# Backplane.net
KiCad netlist of a schematic drawn in EAGLE
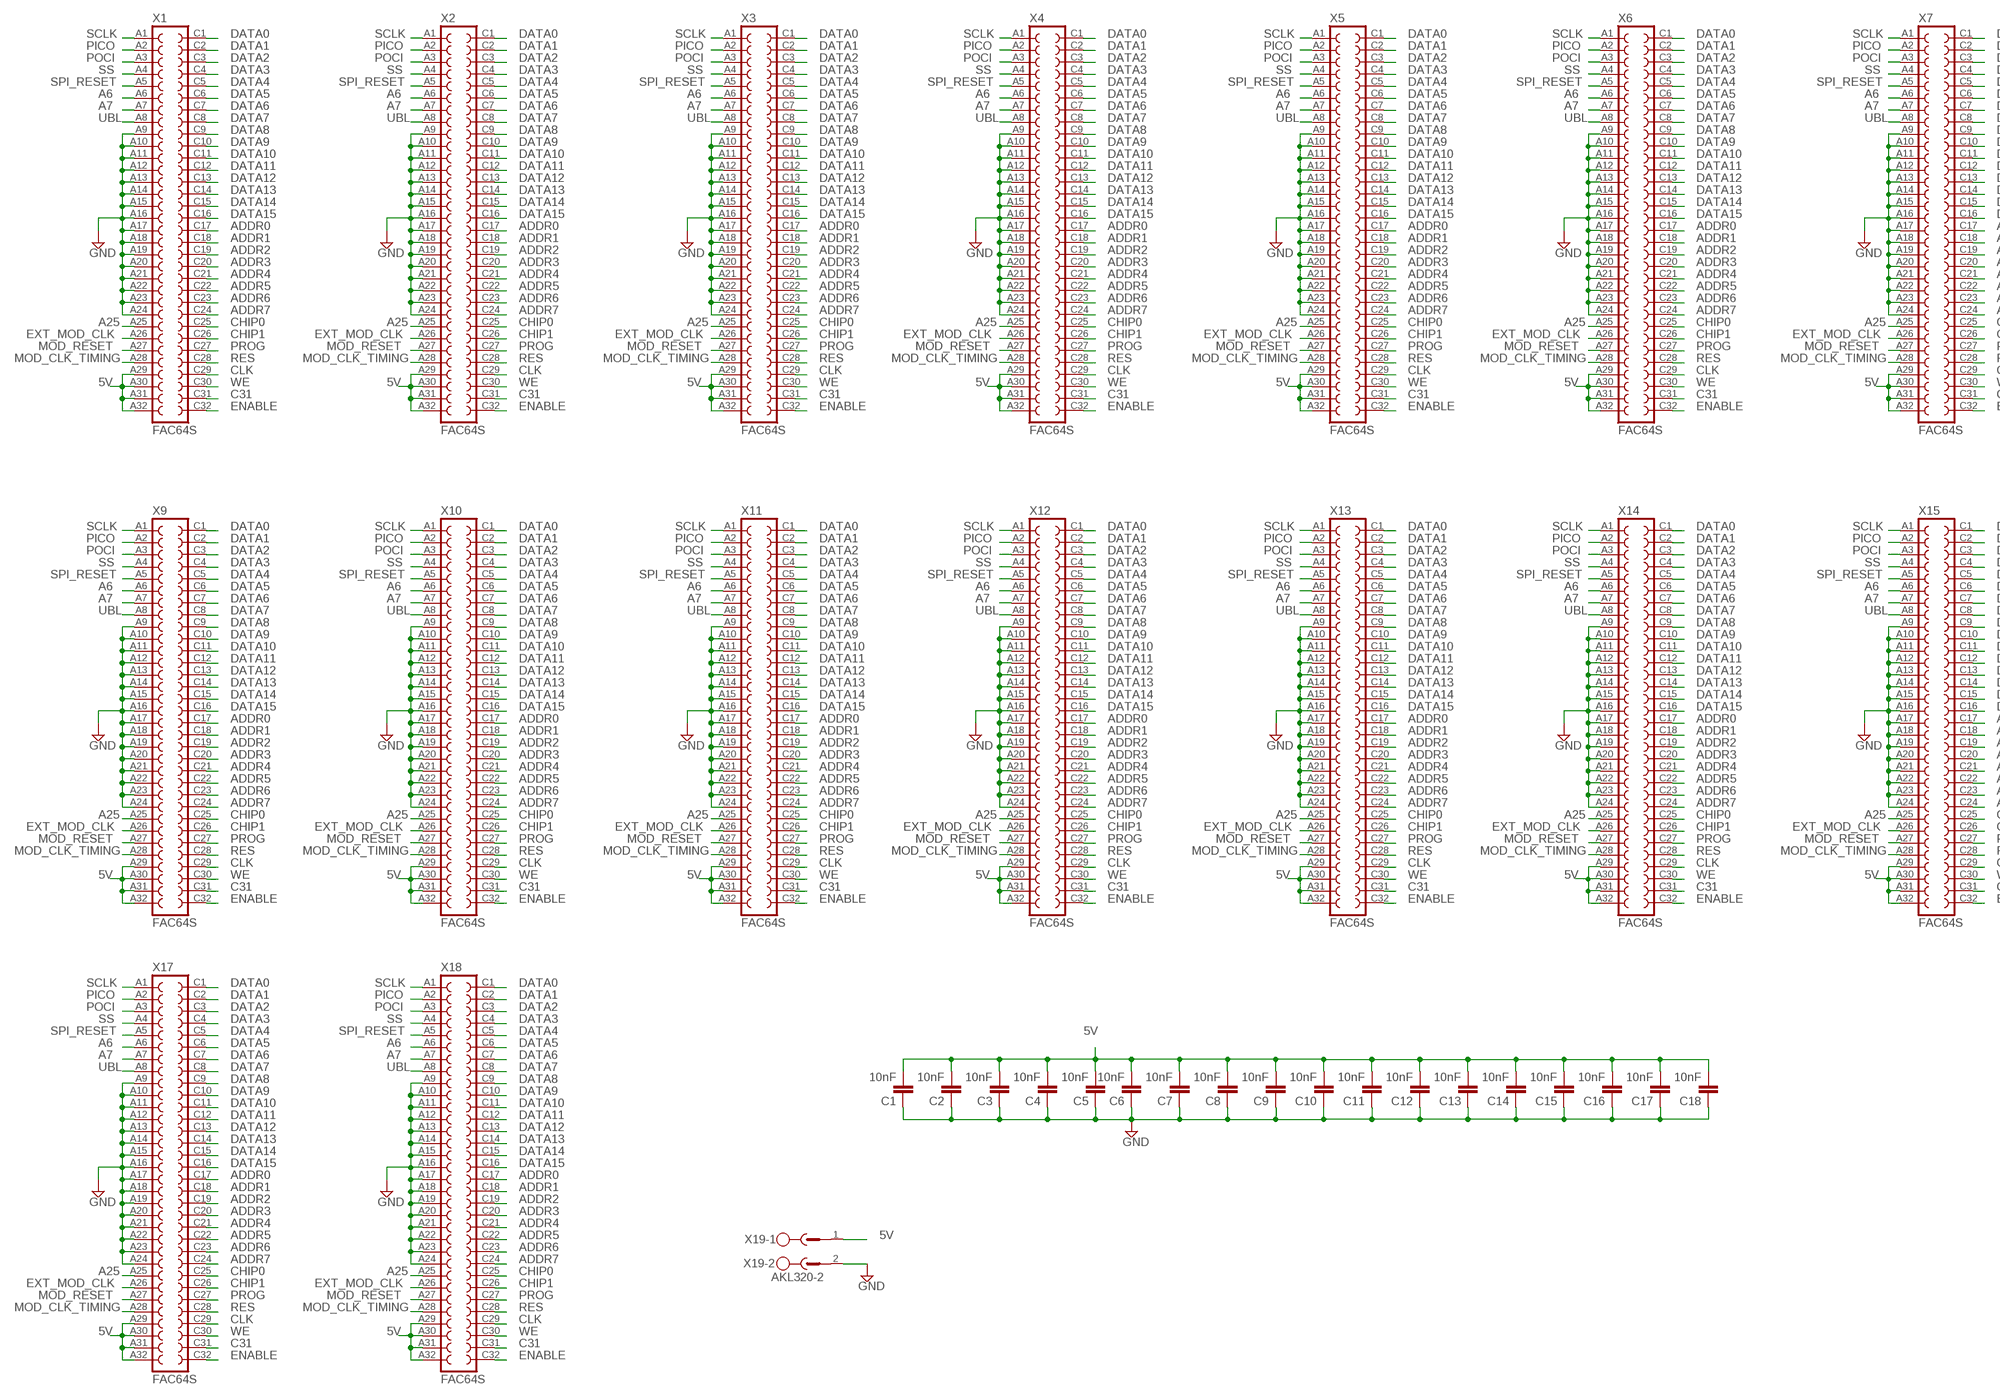
[diagram p0: schematic, sheet 1, part 1 of 2]
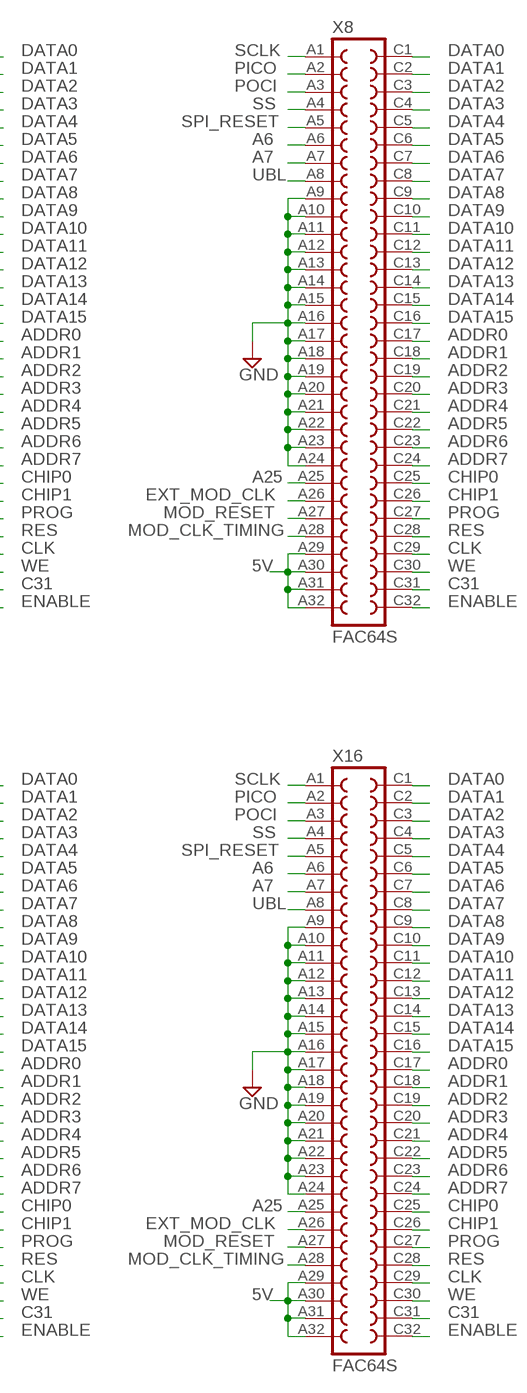
[diagram p1: schematic, sheet 1, part 2 of 2]

(export (version "E")
  (design (tool "Eeschema 10.0.6"))
  (components
    (comp (ref "C1")
      (value "10nF")
      (footprint "eagle-import:C0603")
      (libsource (lib "eagle-import") (part "C-EUC0603"))
    )
    (comp (ref "C2")
      (value "10nF")
      (footprint "eagle-import:C0603")
      (libsource (lib "eagle-import") (part "C-EUC0603"))
    )
    (comp (ref "C3")
      (value "10nF")
      (footprint "eagle-import:C0603")
      (libsource (lib "eagle-import") (part "C-EUC0603"))
    )
    (comp (ref "C4")
      (value "10nF")
      (footprint "eagle-import:C0603")
      (libsource (lib "eagle-import") (part "C-EUC0603"))
    )
    (comp (ref "C5")
      (value "10nF")
      (footprint "eagle-import:C0603")
      (libsource (lib "eagle-import") (part "C-EUC0603"))
    )
    (comp (ref "C6")
      (value "10nF")
      (footprint "eagle-import:C0603")
      (libsource (lib "eagle-import") (part "C-EUC0603"))
    )
    (comp (ref "C7")
      (value "10nF")
      (footprint "eagle-import:C0603")
      (libsource (lib "eagle-import") (part "C-EUC0603"))
    )
    (comp (ref "C8")
      (value "10nF")
      (footprint "eagle-import:C0603")
      (libsource (lib "eagle-import") (part "C-EUC0603"))
    )
    (comp (ref "C9")
      (value "10nF")
      (footprint "eagle-import:C0603")
      (libsource (lib "eagle-import") (part "C-EUC0603"))
    )
    (comp (ref "C10")
      (value "10nF")
      (footprint "eagle-import:C0603")
      (libsource (lib "eagle-import") (part "C-EUC0603"))
    )
    (comp (ref "C11")
      (value "10nF")
      (footprint "eagle-import:C0603")
      (libsource (lib "eagle-import") (part "C-EUC0603"))
    )
    (comp (ref "C12")
      (value "10nF")
      (footprint "eagle-import:C0603")
      (libsource (lib "eagle-import") (part "C-EUC0603"))
    )
    (comp (ref "C13")
      (value "10nF")
      (footprint "eagle-import:C0603")
      (libsource (lib "eagle-import") (part "C-EUC0603"))
    )
    (comp (ref "C14")
      (value "10nF")
      (footprint "eagle-import:C0603")
      (libsource (lib "eagle-import") (part "C-EUC0603"))
    )
    (comp (ref "C15")
      (value "10nF")
      (footprint "eagle-import:C0603")
      (libsource (lib "eagle-import") (part "C-EUC0603"))
    )
    (comp (ref "C16")
      (value "10nF")
      (footprint "eagle-import:C0603")
      (libsource (lib "eagle-import") (part "C-EUC0603"))
    )
    (comp (ref "C17")
      (value "10nF")
      (footprint "eagle-import:C0603")
      (libsource (lib "eagle-import") (part "C-EUC0603"))
    )
    (comp (ref "C18")
      (value "10nF")
      (footprint "eagle-import:C0603")
      (libsource (lib "eagle-import") (part "C-EUC0603"))
    )
    (comp (ref "X1")
      (value "FAC64S")
      (footprint "eagle-import:FAC64S")
      (libsource (lib "eagle-import") (part "FAC64S"))
    )
    (comp (ref "X2")
      (value "FAC64S")
      (footprint "eagle-import:FAC64S")
      (libsource (lib "eagle-import") (part "FAC64S"))
    )
    (comp (ref "X3")
      (value "FAC64S")
      (footprint "eagle-import:FAC64S")
      (libsource (lib "eagle-import") (part "FAC64S"))
    )
    (comp (ref "X4")
      (value "FAC64S")
      (footprint "eagle-import:FAC64S")
      (libsource (lib "eagle-import") (part "FAC64S"))
    )
    (comp (ref "X5")
      (value "FAC64S")
      (footprint "eagle-import:FAC64S")
      (libsource (lib "eagle-import") (part "FAC64S"))
    )
    (comp (ref "X6")
      (value "FAC64S")
      (footprint "eagle-import:FAC64S")
      (libsource (lib "eagle-import") (part "FAC64S"))
    )
    (comp (ref "X7")
      (value "FAC64S")
      (footprint "eagle-import:FAC64S")
      (libsource (lib "eagle-import") (part "FAC64S"))
    )
    (comp (ref "X8")
      (value "FAC64S")
      (footprint "eagle-import:FAC64S")
      (libsource (lib "eagle-import") (part "FAC64S"))
    )
    (comp (ref "X9")
      (value "FAC64S")
      (footprint "eagle-import:FAC64S")
      (libsource (lib "eagle-import") (part "FAC64S"))
    )
    (comp (ref "X10")
      (value "FAC64S")
      (footprint "eagle-import:FAC64S")
      (libsource (lib "eagle-import") (part "FAC64S"))
    )
    (comp (ref "X11")
      (value "FAC64S")
      (footprint "eagle-import:FAC64S")
      (libsource (lib "eagle-import") (part "FAC64S"))
    )
    (comp (ref "X12")
      (value "FAC64S")
      (footprint "eagle-import:FAC64S")
      (libsource (lib "eagle-import") (part "FAC64S"))
    )
    (comp (ref "X13")
      (value "FAC64S")
      (footprint "eagle-import:FAC64S")
      (libsource (lib "eagle-import") (part "FAC64S"))
    )
    (comp (ref "X14")
      (value "FAC64S")
      (footprint "eagle-import:FAC64S")
      (libsource (lib "eagle-import") (part "FAC64S"))
    )
    (comp (ref "X15")
      (value "FAC64S")
      (footprint "eagle-import:FAC64S")
      (libsource (lib "eagle-import") (part "FAC64S"))
    )
    (comp (ref "X16")
      (value "FAC64S")
      (footprint "eagle-import:FAC64S")
      (libsource (lib "eagle-import") (part "FAC64S"))
    )
    (comp (ref "X17")
      (value "FAC64S")
      (footprint "eagle-import:FAC64S")
      (libsource (lib "eagle-import") (part "FAC64S"))
    )
    (comp (ref "X18")
      (value "FAC64S")
      (footprint "eagle-import:FAC64S")
      (libsource (lib "eagle-import") (part "FAC64S"))
    )
    (comp (ref "X19")
      (value "AKL320-2")
      (footprint "eagle-import:MSTBV2")
      (libsource (lib "eagle-import") (part "MSTBV2"))
    )
  )
  (nets
    (net (code "1") (name "/5V") (class "Default")
      (node (ref "C1") (pin "2") (pinfunction "2_2") (pintype "passive"))
      (node (ref "C10") (pin "2") (pinfunction "2_2") (pintype "passive"))
      (node (ref "C11") (pin "2") (pinfunction "2_2") (pintype "passive"))
      (node (ref "C12") (pin "2") (pinfunction "2_2") (pintype "passive"))
      (node (ref "C13") (pin "2") (pinfunction "2_2") (pintype "passive"))
      (node (ref "C14") (pin "2") (pinfunction "2_2") (pintype "passive"))
      (node (ref "C15") (pin "2") (pinfunction "2_2") (pintype "passive"))
      (node (ref "C16") (pin "2") (pinfunction "2_2") (pintype "passive"))
      (node (ref "C17") (pin "2") (pinfunction "2_2") (pintype "passive"))
      (node (ref "C18") (pin "2") (pinfunction "2_2") (pintype "passive"))
      (node (ref "C2") (pin "2") (pinfunction "2_2") (pintype "passive"))
      (node (ref "C3") (pin "2") (pinfunction "2_2") (pintype "passive"))
      (node (ref "C4") (pin "2") (pinfunction "2_2") (pintype "passive"))
      (node (ref "C5") (pin "2") (pinfunction "2_2") (pintype "passive"))
      (node (ref "C6") (pin "2") (pinfunction "2_2") (pintype "passive"))
      (node (ref "C7") (pin "2") (pinfunction "2_2") (pintype "passive"))
      (node (ref "C8") (pin "2") (pinfunction "2_2") (pintype "passive"))
      (node (ref "C9") (pin "2") (pinfunction "2_2") (pintype "passive"))
      (node (ref "X1") (pin "A29") (pinfunction "A29_A29") (pintype "passive"))
      (node (ref "X1") (pin "A30") (pinfunction "A30_A30") (pintype "passive"))
      (node (ref "X1") (pin "A31") (pinfunction "A31_A31") (pintype "passive"))
      (node (ref "X1") (pin "A32") (pinfunction "A32_A32") (pintype "passive"))
      (node (ref "X10") (pin "A29") (pinfunction "A29_A29") (pintype "passive"))
      (node (ref "X10") (pin "A30") (pinfunction "A30_A30") (pintype "passive"))
      (node (ref "X10") (pin "A31") (pinfunction "A31_A31") (pintype "passive"))
      (node (ref "X10") (pin "A32") (pinfunction "A32_A32") (pintype "passive"))
      (node (ref "X11") (pin "A29") (pinfunction "A29_A29") (pintype "passive"))
      (node (ref "X11") (pin "A30") (pinfunction "A30_A30") (pintype "passive"))
      (node (ref "X11") (pin "A31") (pinfunction "A31_A31") (pintype "passive"))
      (node (ref "X11") (pin "A32") (pinfunction "A32_A32") (pintype "passive"))
      (node (ref "X12") (pin "A29") (pinfunction "A29_A29") (pintype "passive"))
      (node (ref "X12") (pin "A30") (pinfunction "A30_A30") (pintype "passive"))
      (node (ref "X12") (pin "A31") (pinfunction "A31_A31") (pintype "passive"))
      (node (ref "X12") (pin "A32") (pinfunction "A32_A32") (pintype "passive"))
      (node (ref "X13") (pin "A29") (pinfunction "A29_A29") (pintype "passive"))
      (node (ref "X13") (pin "A30") (pinfunction "A30_A30") (pintype "passive"))
      (node (ref "X13") (pin "A31") (pinfunction "A31_A31") (pintype "passive"))
      (node (ref "X13") (pin "A32") (pinfunction "A32_A32") (pintype "passive"))
      (node (ref "X14") (pin "A29") (pinfunction "A29_A29") (pintype "passive"))
      (node (ref "X14") (pin "A30") (pinfunction "A30_A30") (pintype "passive"))
      (node (ref "X14") (pin "A31") (pinfunction "A31_A31") (pintype "passive"))
      (node (ref "X14") (pin "A32") (pinfunction "A32_A32") (pintype "passive"))
      (node (ref "X15") (pin "A29") (pinfunction "A29_A29") (pintype "passive"))
      (node (ref "X15") (pin "A30") (pinfunction "A30_A30") (pintype "passive"))
      (node (ref "X15") (pin "A31") (pinfunction "A31_A31") (pintype "passive"))
      (node (ref "X15") (pin "A32") (pinfunction "A32_A32") (pintype "passive"))
      (node (ref "X16") (pin "A29") (pinfunction "A29_A29") (pintype "passive"))
      (node (ref "X16") (pin "A30") (pinfunction "A30_A30") (pintype "passive"))
      (node (ref "X16") (pin "A31") (pinfunction "A31_A31") (pintype "passive"))
      (node (ref "X16") (pin "A32") (pinfunction "A32_A32") (pintype "passive"))
      (node (ref "X17") (pin "A29") (pinfunction "A29_A29") (pintype "passive"))
      (node (ref "X17") (pin "A30") (pinfunction "A30_A30") (pintype "passive"))
      (node (ref "X17") (pin "A31") (pinfunction "A31_A31") (pintype "passive"))
      (node (ref "X17") (pin "A32") (pinfunction "A32_A32") (pintype "passive"))
      (node (ref "X18") (pin "A29") (pinfunction "A29_A29") (pintype "passive"))
      (node (ref "X18") (pin "A30") (pinfunction "A30_A30") (pintype "passive"))
      (node (ref "X18") (pin "A31") (pinfunction "A31_A31") (pintype "passive"))
      (node (ref "X18") (pin "A32") (pinfunction "A32_A32") (pintype "passive"))
      (node (ref "X19") (pin "1") (pinfunction "SK_1") (pintype "passive"))
      (node (ref "X2") (pin "A29") (pinfunction "A29_A29") (pintype "passive"))
      (node (ref "X2") (pin "A30") (pinfunction "A30_A30") (pintype "passive"))
      (node (ref "X2") (pin "A31") (pinfunction "A31_A31") (pintype "passive"))
      (node (ref "X2") (pin "A32") (pinfunction "A32_A32") (pintype "passive"))
      (node (ref "X3") (pin "A29") (pinfunction "A29_A29") (pintype "passive"))
      (node (ref "X3") (pin "A30") (pinfunction "A30_A30") (pintype "passive"))
      (node (ref "X3") (pin "A31") (pinfunction "A31_A31") (pintype "passive"))
      (node (ref "X3") (pin "A32") (pinfunction "A32_A32") (pintype "passive"))
      (node (ref "X4") (pin "A29") (pinfunction "A29_A29") (pintype "passive"))
      (node (ref "X4") (pin "A30") (pinfunction "A30_A30") (pintype "passive"))
      (node (ref "X4") (pin "A31") (pinfunction "A31_A31") (pintype "passive"))
      (node (ref "X4") (pin "A32") (pinfunction "A32_A32") (pintype "passive"))
      (node (ref "X5") (pin "A29") (pinfunction "A29_A29") (pintype "passive"))
      (node (ref "X5") (pin "A30") (pinfunction "A30_A30") (pintype "passive"))
      (node (ref "X5") (pin "A31") (pinfunction "A31_A31") (pintype "passive"))
      (node (ref "X5") (pin "A32") (pinfunction "A32_A32") (pintype "passive"))
      (node (ref "X6") (pin "A29") (pinfunction "A29_A29") (pintype "passive"))
      (node (ref "X6") (pin "A30") (pinfunction "A30_A30") (pintype "passive"))
      (node (ref "X6") (pin "A31") (pinfunction "A31_A31") (pintype "passive"))
      (node (ref "X6") (pin "A32") (pinfunction "A32_A32") (pintype "passive"))
      (node (ref "X7") (pin "A29") (pinfunction "A29_A29") (pintype "passive"))
      (node (ref "X7") (pin "A30") (pinfunction "A30_A30") (pintype "passive"))
      (node (ref "X7") (pin "A31") (pinfunction "A31_A31") (pintype "passive"))
      (node (ref "X7") (pin "A32") (pinfunction "A32_A32") (pintype "passive"))
      (node (ref "X8") (pin "A29") (pinfunction "A29_A29") (pintype "passive"))
      (node (ref "X8") (pin "A30") (pinfunction "A30_A30") (pintype "passive"))
      (node (ref "X8") (pin "A31") (pinfunction "A31_A31") (pintype "passive"))
      (node (ref "X8") (pin "A32") (pinfunction "A32_A32") (pintype "passive"))
      (node (ref "X9") (pin "A29") (pinfunction "A29_A29") (pintype "passive"))
      (node (ref "X9") (pin "A30") (pinfunction "A30_A30") (pintype "passive"))
      (node (ref "X9") (pin "A31") (pinfunction "A31_A31") (pintype "passive"))
      (node (ref "X9") (pin "A32") (pinfunction "A32_A32") (pintype "passive"))
    )
    (net (code "2") (name "/A6") (class "Default")
      (node (ref "X1") (pin "A6") (pinfunction "A6_A6") (pintype "passive"))
      (node (ref "X10") (pin "A6") (pinfunction "A6_A6") (pintype "passive"))
      (node (ref "X11") (pin "A6") (pinfunction "A6_A6") (pintype "passive"))
      (node (ref "X12") (pin "A6") (pinfunction "A6_A6") (pintype "passive"))
      (node (ref "X13") (pin "A6") (pinfunction "A6_A6") (pintype "passive"))
      (node (ref "X14") (pin "A6") (pinfunction "A6_A6") (pintype "passive"))
      (node (ref "X15") (pin "A6") (pinfunction "A6_A6") (pintype "passive"))
      (node (ref "X16") (pin "A6") (pinfunction "A6_A6") (pintype "passive"))
      (node (ref "X17") (pin "A6") (pinfunction "A6_A6") (pintype "passive"))
      (node (ref "X18") (pin "A6") (pinfunction "A6_A6") (pintype "passive"))
      (node (ref "X2") (pin "A6") (pinfunction "A6_A6") (pintype "passive"))
      (node (ref "X3") (pin "A6") (pinfunction "A6_A6") (pintype "passive"))
      (node (ref "X4") (pin "A6") (pinfunction "A6_A6") (pintype "passive"))
      (node (ref "X5") (pin "A6") (pinfunction "A6_A6") (pintype "passive"))
      (node (ref "X6") (pin "A6") (pinfunction "A6_A6") (pintype "passive"))
      (node (ref "X7") (pin "A6") (pinfunction "A6_A6") (pintype "passive"))
      (node (ref "X8") (pin "A6") (pinfunction "A6_A6") (pintype "passive"))
      (node (ref "X9") (pin "A6") (pinfunction "A6_A6") (pintype "passive"))
    )
    (net (code "3") (name "/A7") (class "Default")
      (node (ref "X1") (pin "A7") (pinfunction "A7_A7") (pintype "passive"))
      (node (ref "X10") (pin "A7") (pinfunction "A7_A7") (pintype "passive"))
      (node (ref "X11") (pin "A7") (pinfunction "A7_A7") (pintype "passive"))
      (node (ref "X12") (pin "A7") (pinfunction "A7_A7") (pintype "passive"))
      (node (ref "X13") (pin "A7") (pinfunction "A7_A7") (pintype "passive"))
      (node (ref "X14") (pin "A7") (pinfunction "A7_A7") (pintype "passive"))
      (node (ref "X15") (pin "A7") (pinfunction "A7_A7") (pintype "passive"))
      (node (ref "X16") (pin "A7") (pinfunction "A7_A7") (pintype "passive"))
      (node (ref "X17") (pin "A7") (pinfunction "A7_A7") (pintype "passive"))
      (node (ref "X18") (pin "A7") (pinfunction "A7_A7") (pintype "passive"))
      (node (ref "X2") (pin "A7") (pinfunction "A7_A7") (pintype "passive"))
      (node (ref "X3") (pin "A7") (pinfunction "A7_A7") (pintype "passive"))
      (node (ref "X4") (pin "A7") (pinfunction "A7_A7") (pintype "passive"))
      (node (ref "X5") (pin "A7") (pinfunction "A7_A7") (pintype "passive"))
      (node (ref "X6") (pin "A7") (pinfunction "A7_A7") (pintype "passive"))
      (node (ref "X7") (pin "A7") (pinfunction "A7_A7") (pintype "passive"))
      (node (ref "X8") (pin "A7") (pinfunction "A7_A7") (pintype "passive"))
      (node (ref "X9") (pin "A7") (pinfunction "A7_A7") (pintype "passive"))
    )
    (net (code "4") (name "/A25") (class "Default")
      (node (ref "X1") (pin "A25") (pinfunction "A25_A25") (pintype "passive"))
      (node (ref "X10") (pin "A25") (pinfunction "A25_A25") (pintype "passive"))
      (node (ref "X11") (pin "A25") (pinfunction "A25_A25") (pintype "passive"))
      (node (ref "X12") (pin "A25") (pinfunction "A25_A25") (pintype "passive"))
      (node (ref "X13") (pin "A25") (pinfunction "A25_A25") (pintype "passive"))
      (node (ref "X14") (pin "A25") (pinfunction "A25_A25") (pintype "passive"))
      (node (ref "X15") (pin "A25") (pinfunction "A25_A25") (pintype "passive"))
      (node (ref "X16") (pin "A25") (pinfunction "A25_A25") (pintype "passive"))
      (node (ref "X17") (pin "A25") (pinfunction "A25_A25") (pintype "passive"))
      (node (ref "X18") (pin "A25") (pinfunction "A25_A25") (pintype "passive"))
      (node (ref "X2") (pin "A25") (pinfunction "A25_A25") (pintype "passive"))
      (node (ref "X3") (pin "A25") (pinfunction "A25_A25") (pintype "passive"))
      (node (ref "X4") (pin "A25") (pinfunction "A25_A25") (pintype "passive"))
      (node (ref "X5") (pin "A25") (pinfunction "A25_A25") (pintype "passive"))
      (node (ref "X6") (pin "A25") (pinfunction "A25_A25") (pintype "passive"))
      (node (ref "X7") (pin "A25") (pinfunction "A25_A25") (pintype "passive"))
      (node (ref "X8") (pin "A25") (pinfunction "A25_A25") (pintype "passive"))
      (node (ref "X9") (pin "A25") (pinfunction "A25_A25") (pintype "passive"))
    )
    (net (code "5") (name "/ADDR0") (class "Default")
      (node (ref "X1") (pin "C17") (pinfunction "C17_C17") (pintype "passive"))
      (node (ref "X10") (pin "C17") (pinfunction "C17_C17") (pintype "passive"))
      (node (ref "X11") (pin "C17") (pinfunction "C17_C17") (pintype "passive"))
      (node (ref "X12") (pin "C17") (pinfunction "C17_C17") (pintype "passive"))
      (node (ref "X13") (pin "C17") (pinfunction "C17_C17") (pintype "passive"))
      (node (ref "X14") (pin "C17") (pinfunction "C17_C17") (pintype "passive"))
      (node (ref "X15") (pin "C17") (pinfunction "C17_C17") (pintype "passive"))
      (node (ref "X16") (pin "C17") (pinfunction "C17_C17") (pintype "passive"))
      (node (ref "X17") (pin "C17") (pinfunction "C17_C17") (pintype "passive"))
      (node (ref "X18") (pin "C17") (pinfunction "C17_C17") (pintype "passive"))
      (node (ref "X2") (pin "C17") (pinfunction "C17_C17") (pintype "passive"))
      (node (ref "X3") (pin "C17") (pinfunction "C17_C17") (pintype "passive"))
      (node (ref "X4") (pin "C17") (pinfunction "C17_C17") (pintype "passive"))
      (node (ref "X5") (pin "C17") (pinfunction "C17_C17") (pintype "passive"))
      (node (ref "X6") (pin "C17") (pinfunction "C17_C17") (pintype "passive"))
      (node (ref "X7") (pin "C17") (pinfunction "C17_C17") (pintype "passive"))
      (node (ref "X8") (pin "C17") (pinfunction "C17_C17") (pintype "passive"))
      (node (ref "X9") (pin "C17") (pinfunction "C17_C17") (pintype "passive"))
    )
    (net (code "6") (name "/ADDR1") (class "Default")
      (node (ref "X1") (pin "C18") (pinfunction "C18_C18") (pintype "passive"))
      (node (ref "X10") (pin "C18") (pinfunction "C18_C18") (pintype "passive"))
      (node (ref "X11") (pin "C18") (pinfunction "C18_C18") (pintype "passive"))
      (node (ref "X12") (pin "C18") (pinfunction "C18_C18") (pintype "passive"))
      (node (ref "X13") (pin "C18") (pinfunction "C18_C18") (pintype "passive"))
      (node (ref "X14") (pin "C18") (pinfunction "C18_C18") (pintype "passive"))
      (node (ref "X15") (pin "C18") (pinfunction "C18_C18") (pintype "passive"))
      (node (ref "X16") (pin "C18") (pinfunction "C18_C18") (pintype "passive"))
      (node (ref "X17") (pin "C18") (pinfunction "C18_C18") (pintype "passive"))
      (node (ref "X18") (pin "C18") (pinfunction "C18_C18") (pintype "passive"))
      (node (ref "X2") (pin "C18") (pinfunction "C18_C18") (pintype "passive"))
      (node (ref "X3") (pin "C18") (pinfunction "C18_C18") (pintype "passive"))
      (node (ref "X4") (pin "C18") (pinfunction "C18_C18") (pintype "passive"))
      (node (ref "X5") (pin "C18") (pinfunction "C18_C18") (pintype "passive"))
      (node (ref "X6") (pin "C18") (pinfunction "C18_C18") (pintype "passive"))
      (node (ref "X7") (pin "C18") (pinfunction "C18_C18") (pintype "passive"))
      (node (ref "X8") (pin "C18") (pinfunction "C18_C18") (pintype "passive"))
      (node (ref "X9") (pin "C18") (pinfunction "C18_C18") (pintype "passive"))
    )
    (net (code "7") (name "/ADDR2") (class "Default")
      (node (ref "X1") (pin "C19") (pinfunction "C19_C19") (pintype "passive"))
      (node (ref "X10") (pin "C19") (pinfunction "C19_C19") (pintype "passive"))
      (node (ref "X11") (pin "C19") (pinfunction "C19_C19") (pintype "passive"))
      (node (ref "X12") (pin "C19") (pinfunction "C19_C19") (pintype "passive"))
      (node (ref "X13") (pin "C19") (pinfunction "C19_C19") (pintype "passive"))
      (node (ref "X14") (pin "C19") (pinfunction "C19_C19") (pintype "passive"))
      (node (ref "X15") (pin "C19") (pinfunction "C19_C19") (pintype "passive"))
      (node (ref "X16") (pin "C19") (pinfunction "C19_C19") (pintype "passive"))
      (node (ref "X17") (pin "C19") (pinfunction "C19_C19") (pintype "passive"))
      (node (ref "X18") (pin "C19") (pinfunction "C19_C19") (pintype "passive"))
      (node (ref "X2") (pin "C19") (pinfunction "C19_C19") (pintype "passive"))
      (node (ref "X3") (pin "C19") (pinfunction "C19_C19") (pintype "passive"))
      (node (ref "X4") (pin "C19") (pinfunction "C19_C19") (pintype "passive"))
      (node (ref "X5") (pin "C19") (pinfunction "C19_C19") (pintype "passive"))
      (node (ref "X6") (pin "C19") (pinfunction "C19_C19") (pintype "passive"))
      (node (ref "X7") (pin "C19") (pinfunction "C19_C19") (pintype "passive"))
      (node (ref "X8") (pin "C19") (pinfunction "C19_C19") (pintype "passive"))
      (node (ref "X9") (pin "C19") (pinfunction "C19_C19") (pintype "passive"))
    )
    (net (code "8") (name "/ADDR3") (class "Default")
      (node (ref "X1") (pin "C20") (pinfunction "C20_C20") (pintype "passive"))
      (node (ref "X10") (pin "C20") (pinfunction "C20_C20") (pintype "passive"))
      (node (ref "X11") (pin "C20") (pinfunction "C20_C20") (pintype "passive"))
      (node (ref "X12") (pin "C20") (pinfunction "C20_C20") (pintype "passive"))
      (node (ref "X13") (pin "C20") (pinfunction "C20_C20") (pintype "passive"))
      (node (ref "X14") (pin "C20") (pinfunction "C20_C20") (pintype "passive"))
      (node (ref "X15") (pin "C20") (pinfunction "C20_C20") (pintype "passive"))
      (node (ref "X16") (pin "C20") (pinfunction "C20_C20") (pintype "passive"))
      (node (ref "X17") (pin "C20") (pinfunction "C20_C20") (pintype "passive"))
      (node (ref "X18") (pin "C20") (pinfunction "C20_C20") (pintype "passive"))
      (node (ref "X2") (pin "C20") (pinfunction "C20_C20") (pintype "passive"))
      (node (ref "X3") (pin "C20") (pinfunction "C20_C20") (pintype "passive"))
      (node (ref "X4") (pin "C20") (pinfunction "C20_C20") (pintype "passive"))
      (node (ref "X5") (pin "C20") (pinfunction "C20_C20") (pintype "passive"))
      (node (ref "X6") (pin "C20") (pinfunction "C20_C20") (pintype "passive"))
      (node (ref "X7") (pin "C20") (pinfunction "C20_C20") (pintype "passive"))
      (node (ref "X8") (pin "C20") (pinfunction "C20_C20") (pintype "passive"))
      (node (ref "X9") (pin "C20") (pinfunction "C20_C20") (pintype "passive"))
    )
    (net (code "9") (name "/ADDR4") (class "Default")
      (node (ref "X1") (pin "C21") (pinfunction "C21_C21") (pintype "passive"))
      (node (ref "X10") (pin "C21") (pinfunction "C21_C21") (pintype "passive"))
      (node (ref "X11") (pin "C21") (pinfunction "C21_C21") (pintype "passive"))
      (node (ref "X12") (pin "C21") (pinfunction "C21_C21") (pintype "passive"))
      (node (ref "X13") (pin "C21") (pinfunction "C21_C21") (pintype "passive"))
      (node (ref "X14") (pin "C21") (pinfunction "C21_C21") (pintype "passive"))
      (node (ref "X15") (pin "C21") (pinfunction "C21_C21") (pintype "passive"))
      (node (ref "X16") (pin "C21") (pinfunction "C21_C21") (pintype "passive"))
      (node (ref "X17") (pin "C21") (pinfunction "C21_C21") (pintype "passive"))
      (node (ref "X18") (pin "C21") (pinfunction "C21_C21") (pintype "passive"))
      (node (ref "X2") (pin "C21") (pinfunction "C21_C21") (pintype "passive"))
      (node (ref "X3") (pin "C21") (pinfunction "C21_C21") (pintype "passive"))
      (node (ref "X4") (pin "C21") (pinfunction "C21_C21") (pintype "passive"))
      (node (ref "X5") (pin "C21") (pinfunction "C21_C21") (pintype "passive"))
      (node (ref "X6") (pin "C21") (pinfunction "C21_C21") (pintype "passive"))
      (node (ref "X7") (pin "C21") (pinfunction "C21_C21") (pintype "passive"))
      (node (ref "X8") (pin "C21") (pinfunction "C21_C21") (pintype "passive"))
      (node (ref "X9") (pin "C21") (pinfunction "C21_C21") (pintype "passive"))
    )
    (net (code "10") (name "/ADDR5") (class "Default")
      (node (ref "X1") (pin "C22") (pinfunction "C22_C22") (pintype "passive"))
      (node (ref "X10") (pin "C22") (pinfunction "C22_C22") (pintype "passive"))
      (node (ref "X11") (pin "C22") (pinfunction "C22_C22") (pintype "passive"))
      (node (ref "X12") (pin "C22") (pinfunction "C22_C22") (pintype "passive"))
      (node (ref "X13") (pin "C22") (pinfunction "C22_C22") (pintype "passive"))
      (node (ref "X14") (pin "C22") (pinfunction "C22_C22") (pintype "passive"))
      (node (ref "X15") (pin "C22") (pinfunction "C22_C22") (pintype "passive"))
      (node (ref "X16") (pin "C22") (pinfunction "C22_C22") (pintype "passive"))
      (node (ref "X17") (pin "C22") (pinfunction "C22_C22") (pintype "passive"))
      (node (ref "X18") (pin "C22") (pinfunction "C22_C22") (pintype "passive"))
      (node (ref "X2") (pin "C22") (pinfunction "C22_C22") (pintype "passive"))
      (node (ref "X3") (pin "C22") (pinfunction "C22_C22") (pintype "passive"))
      (node (ref "X4") (pin "C22") (pinfunction "C22_C22") (pintype "passive"))
      (node (ref "X5") (pin "C22") (pinfunction "C22_C22") (pintype "passive"))
      (node (ref "X6") (pin "C22") (pinfunction "C22_C22") (pintype "passive"))
      (node (ref "X7") (pin "C22") (pinfunction "C22_C22") (pintype "passive"))
      (node (ref "X8") (pin "C22") (pinfunction "C22_C22") (pintype "passive"))
      (node (ref "X9") (pin "C22") (pinfunction "C22_C22") (pintype "passive"))
    )
    (net (code "11") (name "/ADDR6") (class "Default")
      (node (ref "X1") (pin "C23") (pinfunction "C23_C23") (pintype "passive"))
      (node (ref "X10") (pin "C23") (pinfunction "C23_C23") (pintype "passive"))
      (node (ref "X11") (pin "C23") (pinfunction "C23_C23") (pintype "passive"))
      (node (ref "X12") (pin "C23") (pinfunction "C23_C23") (pintype "passive"))
      (node (ref "X13") (pin "C23") (pinfunction "C23_C23") (pintype "passive"))
      (node (ref "X14") (pin "C23") (pinfunction "C23_C23") (pintype "passive"))
      (node (ref "X15") (pin "C23") (pinfunction "C23_C23") (pintype "passive"))
      (node (ref "X16") (pin "C23") (pinfunction "C23_C23") (pintype "passive"))
      (node (ref "X17") (pin "C23") (pinfunction "C23_C23") (pintype "passive"))
      (node (ref "X18") (pin "C23") (pinfunction "C23_C23") (pintype "passive"))
      (node (ref "X2") (pin "C23") (pinfunction "C23_C23") (pintype "passive"))
      (node (ref "X3") (pin "C23") (pinfunction "C23_C23") (pintype "passive"))
      (node (ref "X4") (pin "C23") (pinfunction "C23_C23") (pintype "passive"))
      (node (ref "X5") (pin "C23") (pinfunction "C23_C23") (pintype "passive"))
      (node (ref "X6") (pin "C23") (pinfunction "C23_C23") (pintype "passive"))
      (node (ref "X7") (pin "C23") (pinfunction "C23_C23") (pintype "passive"))
      (node (ref "X8") (pin "C23") (pinfunction "C23_C23") (pintype "passive"))
      (node (ref "X9") (pin "C23") (pinfunction "C23_C23") (pintype "passive"))
    )
    (net (code "12") (name "/ADDR7") (class "Default")
      (node (ref "X1") (pin "C24") (pinfunction "C24_C24") (pintype "passive"))
      (node (ref "X10") (pin "C24") (pinfunction "C24_C24") (pintype "passive"))
      (node (ref "X11") (pin "C24") (pinfunction "C24_C24") (pintype "passive"))
      (node (ref "X12") (pin "C24") (pinfunction "C24_C24") (pintype "passive"))
      (node (ref "X13") (pin "C24") (pinfunction "C24_C24") (pintype "passive"))
      (node (ref "X14") (pin "C24") (pinfunction "C24_C24") (pintype "passive"))
      (node (ref "X15") (pin "C24") (pinfunction "C24_C24") (pintype "passive"))
      (node (ref "X16") (pin "C24") (pinfunction "C24_C24") (pintype "passive"))
      (node (ref "X17") (pin "C24") (pinfunction "C24_C24") (pintype "passive"))
      (node (ref "X18") (pin "C24") (pinfunction "C24_C24") (pintype "passive"))
      (node (ref "X2") (pin "C24") (pinfunction "C24_C24") (pintype "passive"))
      (node (ref "X3") (pin "C24") (pinfunction "C24_C24") (pintype "passive"))
      (node (ref "X4") (pin "C24") (pinfunction "C24_C24") (pintype "passive"))
      (node (ref "X5") (pin "C24") (pinfunction "C24_C24") (pintype "passive"))
      (node (ref "X6") (pin "C24") (pinfunction "C24_C24") (pintype "passive"))
      (node (ref "X7") (pin "C24") (pinfunction "C24_C24") (pintype "passive"))
      (node (ref "X8") (pin "C24") (pinfunction "C24_C24") (pintype "passive"))
      (node (ref "X9") (pin "C24") (pinfunction "C24_C24") (pintype "passive"))
    )
    (net (code "13") (name "/C31") (class "Default")
      (node (ref "X1") (pin "C31") (pinfunction "C31_C31") (pintype "passive"))
      (node (ref "X10") (pin "C31") (pinfunction "C31_C31") (pintype "passive"))
      (node (ref "X11") (pin "C31") (pinfunction "C31_C31") (pintype "passive"))
      (node (ref "X12") (pin "C31") (pinfunction "C31_C31") (pintype "passive"))
      (node (ref "X13") (pin "C31") (pinfunction "C31_C31") (pintype "passive"))
      (node (ref "X14") (pin "C31") (pinfunction "C31_C31") (pintype "passive"))
      (node (ref "X15") (pin "C31") (pinfunction "C31_C31") (pintype "passive"))
      (node (ref "X16") (pin "C31") (pinfunction "C31_C31") (pintype "passive"))
      (node (ref "X17") (pin "C31") (pinfunction "C31_C31") (pintype "passive"))
      (node (ref "X18") (pin "C31") (pinfunction "C31_C31") (pintype "passive"))
      (node (ref "X2") (pin "C31") (pinfunction "C31_C31") (pintype "passive"))
      (node (ref "X3") (pin "C31") (pinfunction "C31_C31") (pintype "passive"))
      (node (ref "X4") (pin "C31") (pinfunction "C31_C31") (pintype "passive"))
      (node (ref "X5") (pin "C31") (pinfunction "C31_C31") (pintype "passive"))
      (node (ref "X6") (pin "C31") (pinfunction "C31_C31") (pintype "passive"))
      (node (ref "X7") (pin "C31") (pinfunction "C31_C31") (pintype "passive"))
      (node (ref "X8") (pin "C31") (pinfunction "C31_C31") (pintype "passive"))
      (node (ref "X9") (pin "C31") (pinfunction "C31_C31") (pintype "passive"))
    )
    (net (code "14") (name "/CHIP0") (class "Default")
      (node (ref "X1") (pin "C25") (pinfunction "C25_C25") (pintype "passive"))
      (node (ref "X10") (pin "C25") (pinfunction "C25_C25") (pintype "passive"))
      (node (ref "X11") (pin "C25") (pinfunction "C25_C25") (pintype "passive"))
      (node (ref "X12") (pin "C25") (pinfunction "C25_C25") (pintype "passive"))
      (node (ref "X13") (pin "C25") (pinfunction "C25_C25") (pintype "passive"))
      (node (ref "X14") (pin "C25") (pinfunction "C25_C25") (pintype "passive"))
      (node (ref "X15") (pin "C25") (pinfunction "C25_C25") (pintype "passive"))
      (node (ref "X16") (pin "C25") (pinfunction "C25_C25") (pintype "passive"))
      (node (ref "X17") (pin "C25") (pinfunction "C25_C25") (pintype "passive"))
      (node (ref "X18") (pin "C25") (pinfunction "C25_C25") (pintype "passive"))
      (node (ref "X2") (pin "C25") (pinfunction "C25_C25") (pintype "passive"))
      (node (ref "X3") (pin "C25") (pinfunction "C25_C25") (pintype "passive"))
      (node (ref "X4") (pin "C25") (pinfunction "C25_C25") (pintype "passive"))
      (node (ref "X5") (pin "C25") (pinfunction "C25_C25") (pintype "passive"))
      (node (ref "X6") (pin "C25") (pinfunction "C25_C25") (pintype "passive"))
      (node (ref "X7") (pin "C25") (pinfunction "C25_C25") (pintype "passive"))
      (node (ref "X8") (pin "C25") (pinfunction "C25_C25") (pintype "passive"))
      (node (ref "X9") (pin "C25") (pinfunction "C25_C25") (pintype "passive"))
    )
    (net (code "15") (name "/CHIP1") (class "Default")
      (node (ref "X1") (pin "C26") (pinfunction "C26_C26") (pintype "passive"))
      (node (ref "X10") (pin "C26") (pinfunction "C26_C26") (pintype "passive"))
      (node (ref "X11") (pin "C26") (pinfunction "C26_C26") (pintype "passive"))
      (node (ref "X12") (pin "C26") (pinfunction "C26_C26") (pintype "passive"))
      (node (ref "X13") (pin "C26") (pinfunction "C26_C26") (pintype "passive"))
      (node (ref "X14") (pin "C26") (pinfunction "C26_C26") (pintype "passive"))
      (node (ref "X15") (pin "C26") (pinfunction "C26_C26") (pintype "passive"))
      (node (ref "X16") (pin "C26") (pinfunction "C26_C26") (pintype "passive"))
      (node (ref "X17") (pin "C26") (pinfunction "C26_C26") (pintype "passive"))
      (node (ref "X18") (pin "C26") (pinfunction "C26_C26") (pintype "passive"))
      (node (ref "X2") (pin "C26") (pinfunction "C26_C26") (pintype "passive"))
      (node (ref "X3") (pin "C26") (pinfunction "C26_C26") (pintype "passive"))
      (node (ref "X4") (pin "C26") (pinfunction "C26_C26") (pintype "passive"))
      (node (ref "X5") (pin "C26") (pinfunction "C26_C26") (pintype "passive"))
      (node (ref "X6") (pin "C26") (pinfunction "C26_C26") (pintype "passive"))
      (node (ref "X7") (pin "C26") (pinfunction "C26_C26") (pintype "passive"))
      (node (ref "X8") (pin "C26") (pinfunction "C26_C26") (pintype "passive"))
      (node (ref "X9") (pin "C26") (pinfunction "C26_C26") (pintype "passive"))
    )
    (net (code "16") (name "/CLK") (class "Default")
      (node (ref "X1") (pin "C29") (pinfunction "C29_C29") (pintype "passive"))
      (node (ref "X10") (pin "C29") (pinfunction "C29_C29") (pintype "passive"))
      (node (ref "X11") (pin "C29") (pinfunction "C29_C29") (pintype "passive"))
      (node (ref "X12") (pin "C29") (pinfunction "C29_C29") (pintype "passive"))
      (node (ref "X13") (pin "C29") (pinfunction "C29_C29") (pintype "passive"))
      (node (ref "X14") (pin "C29") (pinfunction "C29_C29") (pintype "passive"))
      (node (ref "X15") (pin "C29") (pinfunction "C29_C29") (pintype "passive"))
      (node (ref "X16") (pin "C29") (pinfunction "C29_C29") (pintype "passive"))
      (node (ref "X17") (pin "C29") (pinfunction "C29_C29") (pintype "passive"))
      (node (ref "X18") (pin "C29") (pinfunction "C29_C29") (pintype "passive"))
      (node (ref "X2") (pin "C29") (pinfunction "C29_C29") (pintype "passive"))
      (node (ref "X3") (pin "C29") (pinfunction "C29_C29") (pintype "passive"))
      (node (ref "X4") (pin "C29") (pinfunction "C29_C29") (pintype "passive"))
      (node (ref "X5") (pin "C29") (pinfunction "C29_C29") (pintype "passive"))
      (node (ref "X6") (pin "C29") (pinfunction "C29_C29") (pintype "passive"))
      (node (ref "X7") (pin "C29") (pinfunction "C29_C29") (pintype "passive"))
      (node (ref "X8") (pin "C29") (pinfunction "C29_C29") (pintype "passive"))
      (node (ref "X9") (pin "C29") (pinfunction "C29_C29") (pintype "passive"))
    )
    (net (code "17") (name "/DATA0") (class "Default")
      (node (ref "X1") (pin "C1") (pinfunction "C1_C1") (pintype "passive"))
      (node (ref "X10") (pin "C1") (pinfunction "C1_C1") (pintype "passive"))
      (node (ref "X11") (pin "C1") (pinfunction "C1_C1") (pintype "passive"))
      (node (ref "X12") (pin "C1") (pinfunction "C1_C1") (pintype "passive"))
      (node (ref "X13") (pin "C1") (pinfunction "C1_C1") (pintype "passive"))
      (node (ref "X14") (pin "C1") (pinfunction "C1_C1") (pintype "passive"))
      (node (ref "X15") (pin "C1") (pinfunction "C1_C1") (pintype "passive"))
      (node (ref "X16") (pin "C1") (pinfunction "C1_C1") (pintype "passive"))
      (node (ref "X17") (pin "C1") (pinfunction "C1_C1") (pintype "passive"))
      (node (ref "X18") (pin "C1") (pinfunction "C1_C1") (pintype "passive"))
      (node (ref "X2") (pin "C1") (pinfunction "C1_C1") (pintype "passive"))
      (node (ref "X3") (pin "C1") (pinfunction "C1_C1") (pintype "passive"))
      (node (ref "X4") (pin "C1") (pinfunction "C1_C1") (pintype "passive"))
      (node (ref "X5") (pin "C1") (pinfunction "C1_C1") (pintype "passive"))
      (node (ref "X6") (pin "C1") (pinfunction "C1_C1") (pintype "passive"))
      (node (ref "X7") (pin "C1") (pinfunction "C1_C1") (pintype "passive"))
      (node (ref "X8") (pin "C1") (pinfunction "C1_C1") (pintype "passive"))
      (node (ref "X9") (pin "C1") (pinfunction "C1_C1") (pintype "passive"))
    )
    (net (code "18") (name "/DATA1") (class "Default")
      (node (ref "X1") (pin "C2") (pinfunction "C2_C2") (pintype "passive"))
      (node (ref "X10") (pin "C2") (pinfunction "C2_C2") (pintype "passive"))
      (node (ref "X11") (pin "C2") (pinfunction "C2_C2") (pintype "passive"))
      (node (ref "X12") (pin "C2") (pinfunction "C2_C2") (pintype "passive"))
      (node (ref "X13") (pin "C2") (pinfunction "C2_C2") (pintype "passive"))
      (node (ref "X14") (pin "C2") (pinfunction "C2_C2") (pintype "passive"))
      (node (ref "X15") (pin "C2") (pinfunction "C2_C2") (pintype "passive"))
      (node (ref "X16") (pin "C2") (pinfunction "C2_C2") (pintype "passive"))
      (node (ref "X17") (pin "C2") (pinfunction "C2_C2") (pintype "passive"))
      (node (ref "X18") (pin "C2") (pinfunction "C2_C2") (pintype "passive"))
      (node (ref "X2") (pin "C2") (pinfunction "C2_C2") (pintype "passive"))
      (node (ref "X3") (pin "C2") (pinfunction "C2_C2") (pintype "passive"))
      (node (ref "X4") (pin "C2") (pinfunction "C2_C2") (pintype "passive"))
      (node (ref "X5") (pin "C2") (pinfunction "C2_C2") (pintype "passive"))
      (node (ref "X6") (pin "C2") (pinfunction "C2_C2") (pintype "passive"))
      (node (ref "X7") (pin "C2") (pinfunction "C2_C2") (pintype "passive"))
      (node (ref "X8") (pin "C2") (pinfunction "C2_C2") (pintype "passive"))
      (node (ref "X9") (pin "C2") (pinfunction "C2_C2") (pintype "passive"))
    )
    (net (code "19") (name "/DATA2") (class "Default")
      (node (ref "X1") (pin "C3") (pinfunction "C3_C3") (pintype "passive"))
      (node (ref "X10") (pin "C3") (pinfunction "C3_C3") (pintype "passive"))
      (node (ref "X11") (pin "C3") (pinfunction "C3_C3") (pintype "passive"))
      (node (ref "X12") (pin "C3") (pinfunction "C3_C3") (pintype "passive"))
      (node (ref "X13") (pin "C3") (pinfunction "C3_C3") (pintype "passive"))
      (node (ref "X14") (pin "C3") (pinfunction "C3_C3") (pintype "passive"))
      (node (ref "X15") (pin "C3") (pinfunction "C3_C3") (pintype "passive"))
      (node (ref "X16") (pin "C3") (pinfunction "C3_C3") (pintype "passive"))
      (node (ref "X17") (pin "C3") (pinfunction "C3_C3") (pintype "passive"))
      (node (ref "X18") (pin "C3") (pinfunction "C3_C3") (pintype "passive"))
      (node (ref "X2") (pin "C3") (pinfunction "C3_C3") (pintype "passive"))
      (node (ref "X3") (pin "C3") (pinfunction "C3_C3") (pintype "passive"))
      (node (ref "X4") (pin "C3") (pinfunction "C3_C3") (pintype "passive"))
      (node (ref "X5") (pin "C3") (pinfunction "C3_C3") (pintype "passive"))
      (node (ref "X6") (pin "C3") (pinfunction "C3_C3") (pintype "passive"))
      (node (ref "X7") (pin "C3") (pinfunction "C3_C3") (pintype "passive"))
      (node (ref "X8") (pin "C3") (pinfunction "C3_C3") (pintype "passive"))
      (node (ref "X9") (pin "C3") (pinfunction "C3_C3") (pintype "passive"))
    )
    (net (code "20") (name "/DATA3") (class "Default")
      (node (ref "X1") (pin "C4") (pinfunction "C4_C4") (pintype "passive"))
      (node (ref "X10") (pin "C4") (pinfunction "C4_C4") (pintype "passive"))
      (node (ref "X11") (pin "C4") (pinfunction "C4_C4") (pintype "passive"))
      (node (ref "X12") (pin "C4") (pinfunction "C4_C4") (pintype "passive"))
      (node (ref "X13") (pin "C4") (pinfunction "C4_C4") (pintype "passive"))
      (node (ref "X14") (pin "C4") (pinfunction "C4_C4") (pintype "passive"))
      (node (ref "X15") (pin "C4") (pinfunction "C4_C4") (pintype "passive"))
      (node (ref "X16") (pin "C4") (pinfunction "C4_C4") (pintype "passive"))
      (node (ref "X17") (pin "C4") (pinfunction "C4_C4") (pintype "passive"))
      (node (ref "X18") (pin "C4") (pinfunction "C4_C4") (pintype "passive"))
      (node (ref "X2") (pin "C4") (pinfunction "C4_C4") (pintype "passive"))
      (node (ref "X3") (pin "C4") (pinfunction "C4_C4") (pintype "passive"))
      (node (ref "X4") (pin "C4") (pinfunction "C4_C4") (pintype "passive"))
      (node (ref "X5") (pin "C4") (pinfunction "C4_C4") (pintype "passive"))
      (node (ref "X6") (pin "C4") (pinfunction "C4_C4") (pintype "passive"))
      (node (ref "X7") (pin "C4") (pinfunction "C4_C4") (pintype "passive"))
      (node (ref "X8") (pin "C4") (pinfunction "C4_C4") (pintype "passive"))
      (node (ref "X9") (pin "C4") (pinfunction "C4_C4") (pintype "passive"))
    )
    (net (code "21") (name "/DATA4") (class "Default")
      (node (ref "X1") (pin "C5") (pinfunction "C5_C5") (pintype "passive"))
      (node (ref "X10") (pin "C5") (pinfunction "C5_C5") (pintype "passive"))
      (node (ref "X11") (pin "C5") (pinfunction "C5_C5") (pintype "passive"))
      (node (ref "X12") (pin "C5") (pinfunction "C5_C5") (pintype "passive"))
      (node (ref "X13") (pin "C5") (pinfunction "C5_C5") (pintype "passive"))
      (node (ref "X14") (pin "C5") (pinfunction "C5_C5") (pintype "passive"))
      (node (ref "X15") (pin "C5") (pinfunction "C5_C5") (pintype "passive"))
      (node (ref "X16") (pin "C5") (pinfunction "C5_C5") (pintype "passive"))
      (node (ref "X17") (pin "C5") (pinfunction "C5_C5") (pintype "passive"))
      (node (ref "X18") (pin "C5") (pinfunction "C5_C5") (pintype "passive"))
      (node (ref "X2") (pin "C5") (pinfunction "C5_C5") (pintype "passive"))
      (node (ref "X3") (pin "C5") (pinfunction "C5_C5") (pintype "passive"))
      (node (ref "X4") (pin "C5") (pinfunction "C5_C5") (pintype "passive"))
      (node (ref "X5") (pin "C5") (pinfunction "C5_C5") (pintype "passive"))
      (node (ref "X6") (pin "C5") (pinfunction "C5_C5") (pintype "passive"))
      (node (ref "X7") (pin "C5") (pinfunction "C5_C5") (pintype "passive"))
      (node (ref "X8") (pin "C5") (pinfunction "C5_C5") (pintype "passive"))
      (node (ref "X9") (pin "C5") (pinfunction "C5_C5") (pintype "passive"))
    )
    (net (code "22") (name "/DATA5") (class "Default")
      (node (ref "X1") (pin "C6") (pinfunction "C6_C6") (pintype "passive"))
      (node (ref "X10") (pin "C6") (pinfunction "C6_C6") (pintype "passive"))
      (node (ref "X11") (pin "C6") (pinfunction "C6_C6") (pintype "passive"))
      (node (ref "X12") (pin "C6") (pinfunction "C6_C6") (pintype "passive"))
      (node (ref "X13") (pin "C6") (pinfunction "C6_C6") (pintype "passive"))
      (node (ref "X14") (pin "C6") (pinfunction "C6_C6") (pintype "passive"))
      (node (ref "X15") (pin "C6") (pinfunction "C6_C6") (pintype "passive"))
      (node (ref "X16") (pin "C6") (pinfunction "C6_C6") (pintype "passive"))
      (node (ref "X17") (pin "C6") (pinfunction "C6_C6") (pintype "passive"))
      (node (ref "X18") (pin "C6") (pinfunction "C6_C6") (pintype "passive"))
      (node (ref "X2") (pin "C6") (pinfunction "C6_C6") (pintype "passive"))
      (node (ref "X3") (pin "C6") (pinfunction "C6_C6") (pintype "passive"))
      (node (ref "X4") (pin "C6") (pinfunction "C6_C6") (pintype "passive"))
      (node (ref "X5") (pin "C6") (pinfunction "C6_C6") (pintype "passive"))
      (node (ref "X6") (pin "C6") (pinfunction "C6_C6") (pintype "passive"))
      (node (ref "X7") (pin "C6") (pinfunction "C6_C6") (pintype "passive"))
      (node (ref "X8") (pin "C6") (pinfunction "C6_C6") (pintype "passive"))
      (node (ref "X9") (pin "C6") (pinfunction "C6_C6") (pintype "passive"))
    )
    (net (code "23") (name "/DATA6") (class "Default")
      (node (ref "X1") (pin "C7") (pinfunction "C7_C7") (pintype "passive"))
      (node (ref "X10") (pin "C7") (pinfunction "C7_C7") (pintype "passive"))
      (node (ref "X11") (pin "C7") (pinfunction "C7_C7") (pintype "passive"))
      (node (ref "X12") (pin "C7") (pinfunction "C7_C7") (pintype "passive"))
      (node (ref "X13") (pin "C7") (pinfunction "C7_C7") (pintype "passive"))
      (node (ref "X14") (pin "C7") (pinfunction "C7_C7") (pintype "passive"))
      (node (ref "X15") (pin "C7") (pinfunction "C7_C7") (pintype "passive"))
      (node (ref "X16") (pin "C7") (pinfunction "C7_C7") (pintype "passive"))
      (node (ref "X17") (pin "C7") (pinfunction "C7_C7") (pintype "passive"))
      (node (ref "X18") (pin "C7") (pinfunction "C7_C7") (pintype "passive"))
      (node (ref "X2") (pin "C7") (pinfunction "C7_C7") (pintype "passive"))
      (node (ref "X3") (pin "C7") (pinfunction "C7_C7") (pintype "passive"))
      (node (ref "X4") (pin "C7") (pinfunction "C7_C7") (pintype "passive"))
      (node (ref "X5") (pin "C7") (pinfunction "C7_C7") (pintype "passive"))
      (node (ref "X6") (pin "C7") (pinfunction "C7_C7") (pintype "passive"))
      (node (ref "X7") (pin "C7") (pinfunction "C7_C7") (pintype "passive"))
      (node (ref "X8") (pin "C7") (pinfunction "C7_C7") (pintype "passive"))
      (node (ref "X9") (pin "C7") (pinfunction "C7_C7") (pintype "passive"))
    )
    (net (code "24") (name "/DATA7") (class "Default")
      (node (ref "X1") (pin "C8") (pinfunction "C8_C8") (pintype "passive"))
      (node (ref "X10") (pin "C8") (pinfunction "C8_C8") (pintype "passive"))
      (node (ref "X11") (pin "C8") (pinfunction "C8_C8") (pintype "passive"))
      (node (ref "X12") (pin "C8") (pinfunction "C8_C8") (pintype "passive"))
      (node (ref "X13") (pin "C8") (pinfunction "C8_C8") (pintype "passive"))
      (node (ref "X14") (pin "C8") (pinfunction "C8_C8") (pintype "passive"))
      (node (ref "X15") (pin "C8") (pinfunction "C8_C8") (pintype "passive"))
      (node (ref "X16") (pin "C8") (pinfunction "C8_C8") (pintype "passive"))
      (node (ref "X17") (pin "C8") (pinfunction "C8_C8") (pintype "passive"))
      (node (ref "X18") (pin "C8") (pinfunction "C8_C8") (pintype "passive"))
      (node (ref "X2") (pin "C8") (pinfunction "C8_C8") (pintype "passive"))
      (node (ref "X3") (pin "C8") (pinfunction "C8_C8") (pintype "passive"))
      (node (ref "X4") (pin "C8") (pinfunction "C8_C8") (pintype "passive"))
      (node (ref "X5") (pin "C8") (pinfunction "C8_C8") (pintype "passive"))
      (node (ref "X6") (pin "C8") (pinfunction "C8_C8") (pintype "passive"))
      (node (ref "X7") (pin "C8") (pinfunction "C8_C8") (pintype "passive"))
      (node (ref "X8") (pin "C8") (pinfunction "C8_C8") (pintype "passive"))
      (node (ref "X9") (pin "C8") (pinfunction "C8_C8") (pintype "passive"))
    )
    (net (code "25") (name "/DATA8") (class "Default")
      (node (ref "X1") (pin "C9") (pinfunction "C9_C9") (pintype "passive"))
      (node (ref "X10") (pin "C9") (pinfunction "C9_C9") (pintype "passive"))
      (node (ref "X11") (pin "C9") (pinfunction "C9_C9") (pintype "passive"))
      (node (ref "X12") (pin "C9") (pinfunction "C9_C9") (pintype "passive"))
      (node (ref "X13") (pin "C9") (pinfunction "C9_C9") (pintype "passive"))
      (node (ref "X14") (pin "C9") (pinfunction "C9_C9") (pintype "passive"))
      (node (ref "X15") (pin "C9") (pinfunction "C9_C9") (pintype "passive"))
      (node (ref "X16") (pin "C9") (pinfunction "C9_C9") (pintype "passive"))
      (node (ref "X17") (pin "C9") (pinfunction "C9_C9") (pintype "passive"))
      (node (ref "X18") (pin "C9") (pinfunction "C9_C9") (pintype "passive"))
      (node (ref "X2") (pin "C9") (pinfunction "C9_C9") (pintype "passive"))
      (node (ref "X3") (pin "C9") (pinfunction "C9_C9") (pintype "passive"))
      (node (ref "X4") (pin "C9") (pinfunction "C9_C9") (pintype "passive"))
      (node (ref "X5") (pin "C9") (pinfunction "C9_C9") (pintype "passive"))
      (node (ref "X6") (pin "C9") (pinfunction "C9_C9") (pintype "passive"))
      (node (ref "X7") (pin "C9") (pinfunction "C9_C9") (pintype "passive"))
      (node (ref "X8") (pin "C9") (pinfunction "C9_C9") (pintype "passive"))
      (node (ref "X9") (pin "C9") (pinfunction "C9_C9") (pintype "passive"))
    )
    (net (code "26") (name "/DATA9") (class "Default")
      (node (ref "X1") (pin "C10") (pinfunction "C10_C10") (pintype "passive"))
      (node (ref "X10") (pin "C10") (pinfunction "C10_C10") (pintype "passive"))
      (node (ref "X11") (pin "C10") (pinfunction "C10_C10") (pintype "passive"))
      (node (ref "X12") (pin "C10") (pinfunction "C10_C10") (pintype "passive"))
      (node (ref "X13") (pin "C10") (pinfunction "C10_C10") (pintype "passive"))
      (node (ref "X14") (pin "C10") (pinfunction "C10_C10") (pintype "passive"))
      (node (ref "X15") (pin "C10") (pinfunction "C10_C10") (pintype "passive"))
      (node (ref "X16") (pin "C10") (pinfunction "C10_C10") (pintype "passive"))
      (node (ref "X17") (pin "C10") (pinfunction "C10_C10") (pintype "passive"))
      (node (ref "X18") (pin "C10") (pinfunction "C10_C10") (pintype "passive"))
      (node (ref "X2") (pin "C10") (pinfunction "C10_C10") (pintype "passive"))
      (node (ref "X3") (pin "C10") (pinfunction "C10_C10") (pintype "passive"))
      (node (ref "X4") (pin "C10") (pinfunction "C10_C10") (pintype "passive"))
      (node (ref "X5") (pin "C10") (pinfunction "C10_C10") (pintype "passive"))
      (node (ref "X6") (pin "C10") (pinfunction "C10_C10") (pintype "passive"))
      (node (ref "X7") (pin "C10") (pinfunction "C10_C10") (pintype "passive"))
      (node (ref "X8") (pin "C10") (pinfunction "C10_C10") (pintype "passive"))
      (node (ref "X9") (pin "C10") (pinfunction "C10_C10") (pintype "passive"))
    )
    (net (code "27") (name "/DATA10") (class "Default")
      (node (ref "X1") (pin "C11") (pinfunction "C11_C11") (pintype "passive"))
      (node (ref "X10") (pin "C11") (pinfunction "C11_C11") (pintype "passive"))
      (node (ref "X11") (pin "C11") (pinfunction "C11_C11") (pintype "passive"))
      (node (ref "X12") (pin "C11") (pinfunction "C11_C11") (pintype "passive"))
      (node (ref "X13") (pin "C11") (pinfunction "C11_C11") (pintype "passive"))
      (node (ref "X14") (pin "C11") (pinfunction "C11_C11") (pintype "passive"))
      (node (ref "X15") (pin "C11") (pinfunction "C11_C11") (pintype "passive"))
      (node (ref "X16") (pin "C11") (pinfunction "C11_C11") (pintype "passive"))
      (node (ref "X17") (pin "C11") (pinfunction "C11_C11") (pintype "passive"))
      (node (ref "X18") (pin "C11") (pinfunction "C11_C11") (pintype "passive"))
      (node (ref "X2") (pin "C11") (pinfunction "C11_C11") (pintype "passive"))
      (node (ref "X3") (pin "C11") (pinfunction "C11_C11") (pintype "passive"))
      (node (ref "X4") (pin "C11") (pinfunction "C11_C11") (pintype "passive"))
      (node (ref "X5") (pin "C11") (pinfunction "C11_C11") (pintype "passive"))
      (node (ref "X6") (pin "C11") (pinfunction "C11_C11") (pintype "passive"))
      (node (ref "X7") (pin "C11") (pinfunction "C11_C11") (pintype "passive"))
      (node (ref "X8") (pin "C11") (pinfunction "C11_C11") (pintype "passive"))
      (node (ref "X9") (pin "C11") (pinfunction "C11_C11") (pintype "passive"))
    )
    (net (code "28") (name "/DATA11") (class "Default")
      (node (ref "X1") (pin "C12") (pinfunction "C12_C12") (pintype "passive"))
      (node (ref "X10") (pin "C12") (pinfunction "C12_C12") (pintype "passive"))
      (node (ref "X11") (pin "C12") (pinfunction "C12_C12") (pintype "passive"))
      (node (ref "X12") (pin "C12") (pinfunction "C12_C12") (pintype "passive"))
      (node (ref "X13") (pin "C12") (pinfunction "C12_C12") (pintype "passive"))
      (node (ref "X14") (pin "C12") (pinfunction "C12_C12") (pintype "passive"))
      (node (ref "X15") (pin "C12") (pinfunction "C12_C12") (pintype "passive"))
      (node (ref "X16") (pin "C12") (pinfunction "C12_C12") (pintype "passive"))
      (node (ref "X17") (pin "C12") (pinfunction "C12_C12") (pintype "passive"))
      (node (ref "X18") (pin "C12") (pinfunction "C12_C12") (pintype "passive"))
      (node (ref "X2") (pin "C12") (pinfunction "C12_C12") (pintype "passive"))
      (node (ref "X3") (pin "C12") (pinfunction "C12_C12") (pintype "passive"))
      (node (ref "X4") (pin "C12") (pinfunction "C12_C12") (pintype "passive"))
      (node (ref "X5") (pin "C12") (pinfunction "C12_C12") (pintype "passive"))
      (node (ref "X6") (pin "C12") (pinfunction "C12_C12") (pintype "passive"))
      (node (ref "X7") (pin "C12") (pinfunction "C12_C12") (pintype "passive"))
      (node (ref "X8") (pin "C12") (pinfunction "C12_C12") (pintype "passive"))
      (node (ref "X9") (pin "C12") (pinfunction "C12_C12") (pintype "passive"))
    )
    (net (code "29") (name "/DATA12") (class "Default")
      (node (ref "X1") (pin "C13") (pinfunction "C13_C13") (pintype "passive"))
      (node (ref "X10") (pin "C13") (pinfunction "C13_C13") (pintype "passive"))
      (node (ref "X11") (pin "C13") (pinfunction "C13_C13") (pintype "passive"))
      (node (ref "X12") (pin "C13") (pinfunction "C13_C13") (pintype "passive"))
      (node (ref "X13") (pin "C13") (pinfunction "C13_C13") (pintype "passive"))
      (node (ref "X14") (pin "C13") (pinfunction "C13_C13") (pintype "passive"))
      (node (ref "X15") (pin "C13") (pinfunction "C13_C13") (pintype "passive"))
      (node (ref "X16") (pin "C13") (pinfunction "C13_C13") (pintype "passive"))
      (node (ref "X17") (pin "C13") (pinfunction "C13_C13") (pintype "passive"))
      (node (ref "X18") (pin "C13") (pinfunction "C13_C13") (pintype "passive"))
      (node (ref "X2") (pin "C13") (pinfunction "C13_C13") (pintype "passive"))
      (node (ref "X3") (pin "C13") (pinfunction "C13_C13") (pintype "passive"))
      (node (ref "X4") (pin "C13") (pinfunction "C13_C13") (pintype "passive"))
      (node (ref "X5") (pin "C13") (pinfunction "C13_C13") (pintype "passive"))
      (node (ref "X6") (pin "C13") (pinfunction "C13_C13") (pintype "passive"))
      (node (ref "X7") (pin "C13") (pinfunction "C13_C13") (pintype "passive"))
      (node (ref "X8") (pin "C13") (pinfunction "C13_C13") (pintype "passive"))
      (node (ref "X9") (pin "C13") (pinfunction "C13_C13") (pintype "passive"))
    )
    (net (code "30") (name "/DATA13") (class "Default")
      (node (ref "X1") (pin "C14") (pinfunction "C14_C14") (pintype "passive"))
      (node (ref "X10") (pin "C14") (pinfunction "C14_C14") (pintype "passive"))
      (node (ref "X11") (pin "C14") (pinfunction "C14_C14") (pintype "passive"))
      (node (ref "X12") (pin "C14") (pinfunction "C14_C14") (pintype "passive"))
      (node (ref "X13") (pin "C14") (pinfunction "C14_C14") (pintype "passive"))
      (node (ref "X14") (pin "C14") (pinfunction "C14_C14") (pintype "passive"))
      (node (ref "X15") (pin "C14") (pinfunction "C14_C14") (pintype "passive"))
      (node (ref "X16") (pin "C14") (pinfunction "C14_C14") (pintype "passive"))
      (node (ref "X17") (pin "C14") (pinfunction "C14_C14") (pintype "passive"))
      (node (ref "X18") (pin "C14") (pinfunction "C14_C14") (pintype "passive"))
      (node (ref "X2") (pin "C14") (pinfunction "C14_C14") (pintype "passive"))
      (node (ref "X3") (pin "C14") (pinfunction "C14_C14") (pintype "passive"))
      (node (ref "X4") (pin "C14") (pinfunction "C14_C14") (pintype "passive"))
      (node (ref "X5") (pin "C14") (pinfunction "C14_C14") (pintype "passive"))
      (node (ref "X6") (pin "C14") (pinfunction "C14_C14") (pintype "passive"))
      (node (ref "X7") (pin "C14") (pinfunction "C14_C14") (pintype "passive"))
      (node (ref "X8") (pin "C14") (pinfunction "C14_C14") (pintype "passive"))
      (node (ref "X9") (pin "C14") (pinfunction "C14_C14") (pintype "passive"))
    )
    (net (code "31") (name "/DATA14") (class "Default")
      (node (ref "X1") (pin "C15") (pinfunction "C15_C15") (pintype "passive"))
      (node (ref "X10") (pin "C15") (pinfunction "C15_C15") (pintype "passive"))
      (node (ref "X11") (pin "C15") (pinfunction "C15_C15") (pintype "passive"))
      (node (ref "X12") (pin "C15") (pinfunction "C15_C15") (pintype "passive"))
      (node (ref "X13") (pin "C15") (pinfunction "C15_C15") (pintype "passive"))
      (node (ref "X14") (pin "C15") (pinfunction "C15_C15") (pintype "passive"))
      (node (ref "X15") (pin "C15") (pinfunction "C15_C15") (pintype "passive"))
      (node (ref "X16") (pin "C15") (pinfunction "C15_C15") (pintype "passive"))
      (node (ref "X17") (pin "C15") (pinfunction "C15_C15") (pintype "passive"))
      (node (ref "X18") (pin "C15") (pinfunction "C15_C15") (pintype "passive"))
      (node (ref "X2") (pin "C15") (pinfunction "C15_C15") (pintype "passive"))
      (node (ref "X3") (pin "C15") (pinfunction "C15_C15") (pintype "passive"))
      (node (ref "X4") (pin "C15") (pinfunction "C15_C15") (pintype "passive"))
      (node (ref "X5") (pin "C15") (pinfunction "C15_C15") (pintype "passive"))
      (node (ref "X6") (pin "C15") (pinfunction "C15_C15") (pintype "passive"))
      (node (ref "X7") (pin "C15") (pinfunction "C15_C15") (pintype "passive"))
      (node (ref "X8") (pin "C15") (pinfunction "C15_C15") (pintype "passive"))
      (node (ref "X9") (pin "C15") (pinfunction "C15_C15") (pintype "passive"))
    )
    (net (code "32") (name "/DATA15") (class "Default")
      (node (ref "X1") (pin "C16") (pinfunction "C16_C16") (pintype "passive"))
      (node (ref "X10") (pin "C16") (pinfunction "C16_C16") (pintype "passive"))
      (node (ref "X11") (pin "C16") (pinfunction "C16_C16") (pintype "passive"))
      (node (ref "X12") (pin "C16") (pinfunction "C16_C16") (pintype "passive"))
      (node (ref "X13") (pin "C16") (pinfunction "C16_C16") (pintype "passive"))
      (node (ref "X14") (pin "C16") (pinfunction "C16_C16") (pintype "passive"))
      (node (ref "X15") (pin "C16") (pinfunction "C16_C16") (pintype "passive"))
      (node (ref "X16") (pin "C16") (pinfunction "C16_C16") (pintype "passive"))
      (node (ref "X17") (pin "C16") (pinfunction "C16_C16") (pintype "passive"))
      (node (ref "X18") (pin "C16") (pinfunction "C16_C16") (pintype "passive"))
      (node (ref "X2") (pin "C16") (pinfunction "C16_C16") (pintype "passive"))
      (node (ref "X3") (pin "C16") (pinfunction "C16_C16") (pintype "passive"))
      (node (ref "X4") (pin "C16") (pinfunction "C16_C16") (pintype "passive"))
      (node (ref "X5") (pin "C16") (pinfunction "C16_C16") (pintype "passive"))
      (node (ref "X6") (pin "C16") (pinfunction "C16_C16") (pintype "passive"))
      (node (ref "X7") (pin "C16") (pinfunction "C16_C16") (pintype "passive"))
      (node (ref "X8") (pin "C16") (pinfunction "C16_C16") (pintype "passive"))
      (node (ref "X9") (pin "C16") (pinfunction "C16_C16") (pintype "passive"))
    )
    (net (code "33") (name "/ENABLE") (class "Default")
      (node (ref "X1") (pin "C32") (pinfunction "C32_C32") (pintype "passive"))
      (node (ref "X10") (pin "C32") (pinfunction "C32_C32") (pintype "passive"))
      (node (ref "X11") (pin "C32") (pinfunction "C32_C32") (pintype "passive"))
      (node (ref "X12") (pin "C32") (pinfunction "C32_C32") (pintype "passive"))
      (node (ref "X13") (pin "C32") (pinfunction "C32_C32") (pintype "passive"))
      (node (ref "X14") (pin "C32") (pinfunction "C32_C32") (pintype "passive"))
      (node (ref "X15") (pin "C32") (pinfunction "C32_C32") (pintype "passive"))
      (node (ref "X16") (pin "C32") (pinfunction "C32_C32") (pintype "passive"))
      (node (ref "X17") (pin "C32") (pinfunction "C32_C32") (pintype "passive"))
      (node (ref "X18") (pin "C32") (pinfunction "C32_C32") (pintype "passive"))
      (node (ref "X2") (pin "C32") (pinfunction "C32_C32") (pintype "passive"))
      (node (ref "X3") (pin "C32") (pinfunction "C32_C32") (pintype "passive"))
      (node (ref "X4") (pin "C32") (pinfunction "C32_C32") (pintype "passive"))
      (node (ref "X5") (pin "C32") (pinfunction "C32_C32") (pintype "passive"))
      (node (ref "X6") (pin "C32") (pinfunction "C32_C32") (pintype "passive"))
      (node (ref "X7") (pin "C32") (pinfunction "C32_C32") (pintype "passive"))
      (node (ref "X8") (pin "C32") (pinfunction "C32_C32") (pintype "passive"))
      (node (ref "X9") (pin "C32") (pinfunction "C32_C32") (pintype "passive"))
    )
    (net (code "34") (name "/EXT_MOD_CLK") (class "Default")
      (node (ref "X1") (pin "A26") (pinfunction "A26_A26") (pintype "passive"))
      (node (ref "X10") (pin "A26") (pinfunction "A26_A26") (pintype "passive"))
      (node (ref "X11") (pin "A26") (pinfunction "A26_A26") (pintype "passive"))
      (node (ref "X12") (pin "A26") (pinfunction "A26_A26") (pintype "passive"))
      (node (ref "X13") (pin "A26") (pinfunction "A26_A26") (pintype "passive"))
      (node (ref "X14") (pin "A26") (pinfunction "A26_A26") (pintype "passive"))
      (node (ref "X15") (pin "A26") (pinfunction "A26_A26") (pintype "passive"))
      (node (ref "X16") (pin "A26") (pinfunction "A26_A26") (pintype "passive"))
      (node (ref "X17") (pin "A26") (pinfunction "A26_A26") (pintype "passive"))
      (node (ref "X18") (pin "A26") (pinfunction "A26_A26") (pintype "passive"))
      (node (ref "X2") (pin "A26") (pinfunction "A26_A26") (pintype "passive"))
      (node (ref "X3") (pin "A26") (pinfunction "A26_A26") (pintype "passive"))
      (node (ref "X4") (pin "A26") (pinfunction "A26_A26") (pintype "passive"))
      (node (ref "X5") (pin "A26") (pinfunction "A26_A26") (pintype "passive"))
      (node (ref "X6") (pin "A26") (pinfunction "A26_A26") (pintype "passive"))
      (node (ref "X7") (pin "A26") (pinfunction "A26_A26") (pintype "passive"))
      (node (ref "X8") (pin "A26") (pinfunction "A26_A26") (pintype "passive"))
      (node (ref "X9") (pin "A26") (pinfunction "A26_A26") (pintype "passive"))
    )
    (net (code "35") (name "/MOD_CLK_TIMING") (class "Default")
      (node (ref "X1") (pin "A28") (pinfunction "A28_A28") (pintype "passive"))
      (node (ref "X10") (pin "A28") (pinfunction "A28_A28") (pintype "passive"))
      (node (ref "X11") (pin "A28") (pinfunction "A28_A28") (pintype "passive"))
      (node (ref "X12") (pin "A28") (pinfunction "A28_A28") (pintype "passive"))
      (node (ref "X13") (pin "A28") (pinfunction "A28_A28") (pintype "passive"))
      (node (ref "X14") (pin "A28") (pinfunction "A28_A28") (pintype "passive"))
      (node (ref "X15") (pin "A28") (pinfunction "A28_A28") (pintype "passive"))
      (node (ref "X16") (pin "A28") (pinfunction "A28_A28") (pintype "passive"))
      (node (ref "X17") (pin "A28") (pinfunction "A28_A28") (pintype "passive"))
      (node (ref "X18") (pin "A28") (pinfunction "A28_A28") (pintype "passive"))
      (node (ref "X2") (pin "A28") (pinfunction "A28_A28") (pintype "passive"))
      (node (ref "X3") (pin "A28") (pinfunction "A28_A28") (pintype "passive"))
      (node (ref "X4") (pin "A28") (pinfunction "A28_A28") (pintype "passive"))
      (node (ref "X5") (pin "A28") (pinfunction "A28_A28") (pintype "passive"))
      (node (ref "X6") (pin "A28") (pinfunction "A28_A28") (pintype "passive"))
      (node (ref "X7") (pin "A28") (pinfunction "A28_A28") (pintype "passive"))
      (node (ref "X8") (pin "A28") (pinfunction "A28_A28") (pintype "passive"))
      (node (ref "X9") (pin "A28") (pinfunction "A28_A28") (pintype "passive"))
    )
    (net (code "36") (name "/MOD_RESET") (class "Default")
      (node (ref "X1") (pin "A27") (pinfunction "A27_A27") (pintype "passive"))
      (node (ref "X10") (pin "A27") (pinfunction "A27_A27") (pintype "passive"))
      (node (ref "X11") (pin "A27") (pinfunction "A27_A27") (pintype "passive"))
      (node (ref "X12") (pin "A27") (pinfunction "A27_A27") (pintype "passive"))
      (node (ref "X13") (pin "A27") (pinfunction "A27_A27") (pintype "passive"))
      (node (ref "X14") (pin "A27") (pinfunction "A27_A27") (pintype "passive"))
      (node (ref "X15") (pin "A27") (pinfunction "A27_A27") (pintype "passive"))
      (node (ref "X16") (pin "A27") (pinfunction "A27_A27") (pintype "passive"))
      (node (ref "X17") (pin "A27") (pinfunction "A27_A27") (pintype "passive"))
      (node (ref "X18") (pin "A27") (pinfunction "A27_A27") (pintype "passive"))
      (node (ref "X2") (pin "A27") (pinfunction "A27_A27") (pintype "passive"))
      (node (ref "X3") (pin "A27") (pinfunction "A27_A27") (pintype "passive"))
      (node (ref "X4") (pin "A27") (pinfunction "A27_A27") (pintype "passive"))
      (node (ref "X5") (pin "A27") (pinfunction "A27_A27") (pintype "passive"))
      (node (ref "X6") (pin "A27") (pinfunction "A27_A27") (pintype "passive"))
      (node (ref "X7") (pin "A27") (pinfunction "A27_A27") (pintype "passive"))
      (node (ref "X8") (pin "A27") (pinfunction "A27_A27") (pintype "passive"))
      (node (ref "X9") (pin "A27") (pinfunction "A27_A27") (pintype "passive"))
    )
    (net (code "37") (name "/PICO") (class "Default")
      (node (ref "X1") (pin "A2") (pinfunction "A2_A2") (pintype "passive"))
      (node (ref "X10") (pin "A2") (pinfunction "A2_A2") (pintype "passive"))
      (node (ref "X11") (pin "A2") (pinfunction "A2_A2") (pintype "passive"))
      (node (ref "X12") (pin "A2") (pinfunction "A2_A2") (pintype "passive"))
      (node (ref "X13") (pin "A2") (pinfunction "A2_A2") (pintype "passive"))
      (node (ref "X14") (pin "A2") (pinfunction "A2_A2") (pintype "passive"))
      (node (ref "X15") (pin "A2") (pinfunction "A2_A2") (pintype "passive"))
      (node (ref "X16") (pin "A2") (pinfunction "A2_A2") (pintype "passive"))
      (node (ref "X17") (pin "A2") (pinfunction "A2_A2") (pintype "passive"))
      (node (ref "X18") (pin "A2") (pinfunction "A2_A2") (pintype "passive"))
      (node (ref "X2") (pin "A2") (pinfunction "A2_A2") (pintype "passive"))
      (node (ref "X3") (pin "A2") (pinfunction "A2_A2") (pintype "passive"))
      (node (ref "X4") (pin "A2") (pinfunction "A2_A2") (pintype "passive"))
      (node (ref "X5") (pin "A2") (pinfunction "A2_A2") (pintype "passive"))
      (node (ref "X6") (pin "A2") (pinfunction "A2_A2") (pintype "passive"))
      (node (ref "X7") (pin "A2") (pinfunction "A2_A2") (pintype "passive"))
      (node (ref "X8") (pin "A2") (pinfunction "A2_A2") (pintype "passive"))
      (node (ref "X9") (pin "A2") (pinfunction "A2_A2") (pintype "passive"))
    )
    (net (code "38") (name "/POCI") (class "Default")
      (node (ref "X1") (pin "A3") (pinfunction "A3_A3") (pintype "passive"))
      (node (ref "X10") (pin "A3") (pinfunction "A3_A3") (pintype "passive"))
      (node (ref "X11") (pin "A3") (pinfunction "A3_A3") (pintype "passive"))
      (node (ref "X12") (pin "A3") (pinfunction "A3_A3") (pintype "passive"))
      (node (ref "X13") (pin "A3") (pinfunction "A3_A3") (pintype "passive"))
      (node (ref "X14") (pin "A3") (pinfunction "A3_A3") (pintype "passive"))
      (node (ref "X15") (pin "A3") (pinfunction "A3_A3") (pintype "passive"))
      (node (ref "X16") (pin "A3") (pinfunction "A3_A3") (pintype "passive"))
      (node (ref "X17") (pin "A3") (pinfunction "A3_A3") (pintype "passive"))
      (node (ref "X18") (pin "A3") (pinfunction "A3_A3") (pintype "passive"))
      (node (ref "X2") (pin "A3") (pinfunction "A3_A3") (pintype "passive"))
      (node (ref "X3") (pin "A3") (pinfunction "A3_A3") (pintype "passive"))
      (node (ref "X4") (pin "A3") (pinfunction "A3_A3") (pintype "passive"))
      (node (ref "X5") (pin "A3") (pinfunction "A3_A3") (pintype "passive"))
      (node (ref "X6") (pin "A3") (pinfunction "A3_A3") (pintype "passive"))
      (node (ref "X7") (pin "A3") (pinfunction "A3_A3") (pintype "passive"))
      (node (ref "X8") (pin "A3") (pinfunction "A3_A3") (pintype "passive"))
      (node (ref "X9") (pin "A3") (pinfunction "A3_A3") (pintype "passive"))
    )
    (net (code "39") (name "/PROG") (class "Default")
      (node (ref "X1") (pin "C27") (pinfunction "C27_C27") (pintype "passive"))
      (node (ref "X10") (pin "C27") (pinfunction "C27_C27") (pintype "passive"))
      (node (ref "X11") (pin "C27") (pinfunction "C27_C27") (pintype "passive"))
      (node (ref "X12") (pin "C27") (pinfunction "C27_C27") (pintype "passive"))
      (node (ref "X13") (pin "C27") (pinfunction "C27_C27") (pintype "passive"))
      (node (ref "X14") (pin "C27") (pinfunction "C27_C27") (pintype "passive"))
      (node (ref "X15") (pin "C27") (pinfunction "C27_C27") (pintype "passive"))
      (node (ref "X16") (pin "C27") (pinfunction "C27_C27") (pintype "passive"))
      (node (ref "X17") (pin "C27") (pinfunction "C27_C27") (pintype "passive"))
      (node (ref "X18") (pin "C27") (pinfunction "C27_C27") (pintype "passive"))
      (node (ref "X2") (pin "C27") (pinfunction "C27_C27") (pintype "passive"))
      (node (ref "X3") (pin "C27") (pinfunction "C27_C27") (pintype "passive"))
      (node (ref "X4") (pin "C27") (pinfunction "C27_C27") (pintype "passive"))
      (node (ref "X5") (pin "C27") (pinfunction "C27_C27") (pintype "passive"))
      (node (ref "X6") (pin "C27") (pinfunction "C27_C27") (pintype "passive"))
      (node (ref "X7") (pin "C27") (pinfunction "C27_C27") (pintype "passive"))
      (node (ref "X8") (pin "C27") (pinfunction "C27_C27") (pintype "passive"))
      (node (ref "X9") (pin "C27") (pinfunction "C27_C27") (pintype "passive"))
    )
    (net (code "40") (name "/RES") (class "Default")
      (node (ref "X1") (pin "C28") (pinfunction "C28_C28") (pintype "passive"))
      (node (ref "X10") (pin "C28") (pinfunction "C28_C28") (pintype "passive"))
      (node (ref "X11") (pin "C28") (pinfunction "C28_C28") (pintype "passive"))
      (node (ref "X12") (pin "C28") (pinfunction "C28_C28") (pintype "passive"))
      (node (ref "X13") (pin "C28") (pinfunction "C28_C28") (pintype "passive"))
      (node (ref "X14") (pin "C28") (pinfunction "C28_C28") (pintype "passive"))
      (node (ref "X15") (pin "C28") (pinfunction "C28_C28") (pintype "passive"))
      (node (ref "X16") (pin "C28") (pinfunction "C28_C28") (pintype "passive"))
      (node (ref "X17") (pin "C28") (pinfunction "C28_C28") (pintype "passive"))
      (node (ref "X18") (pin "C28") (pinfunction "C28_C28") (pintype "passive"))
      (node (ref "X2") (pin "C28") (pinfunction "C28_C28") (pintype "passive"))
      (node (ref "X3") (pin "C28") (pinfunction "C28_C28") (pintype "passive"))
      (node (ref "X4") (pin "C28") (pinfunction "C28_C28") (pintype "passive"))
      (node (ref "X5") (pin "C28") (pinfunction "C28_C28") (pintype "passive"))
      (node (ref "X6") (pin "C28") (pinfunction "C28_C28") (pintype "passive"))
      (node (ref "X7") (pin "C28") (pinfunction "C28_C28") (pintype "passive"))
      (node (ref "X8") (pin "C28") (pinfunction "C28_C28") (pintype "passive"))
      (node (ref "X9") (pin "C28") (pinfunction "C28_C28") (pintype "passive"))
    )
    (net (code "41") (name "/SCLK") (class "Default")
      (node (ref "X1") (pin "A1") (pinfunction "A1_A1") (pintype "passive"))
      (node (ref "X10") (pin "A1") (pinfunction "A1_A1") (pintype "passive"))
      (node (ref "X11") (pin "A1") (pinfunction "A1_A1") (pintype "passive"))
      (node (ref "X12") (pin "A1") (pinfunction "A1_A1") (pintype "passive"))
      (node (ref "X13") (pin "A1") (pinfunction "A1_A1") (pintype "passive"))
      (node (ref "X14") (pin "A1") (pinfunction "A1_A1") (pintype "passive"))
      (node (ref "X15") (pin "A1") (pinfunction "A1_A1") (pintype "passive"))
      (node (ref "X16") (pin "A1") (pinfunction "A1_A1") (pintype "passive"))
      (node (ref "X17") (pin "A1") (pinfunction "A1_A1") (pintype "passive"))
      (node (ref "X18") (pin "A1") (pinfunction "A1_A1") (pintype "passive"))
      (node (ref "X2") (pin "A1") (pinfunction "A1_A1") (pintype "passive"))
      (node (ref "X3") (pin "A1") (pinfunction "A1_A1") (pintype "passive"))
      (node (ref "X4") (pin "A1") (pinfunction "A1_A1") (pintype "passive"))
      (node (ref "X5") (pin "A1") (pinfunction "A1_A1") (pintype "passive"))
      (node (ref "X6") (pin "A1") (pinfunction "A1_A1") (pintype "passive"))
      (node (ref "X7") (pin "A1") (pinfunction "A1_A1") (pintype "passive"))
      (node (ref "X8") (pin "A1") (pinfunction "A1_A1") (pintype "passive"))
      (node (ref "X9") (pin "A1") (pinfunction "A1_A1") (pintype "passive"))
    )
    (net (code "42") (name "/SPI_RESET") (class "Default")
      (node (ref "X1") (pin "A5") (pinfunction "A5_A5") (pintype "passive"))
      (node (ref "X10") (pin "A5") (pinfunction "A5_A5") (pintype "passive"))
      (node (ref "X11") (pin "A5") (pinfunction "A5_A5") (pintype "passive"))
      (node (ref "X12") (pin "A5") (pinfunction "A5_A5") (pintype "passive"))
      (node (ref "X13") (pin "A5") (pinfunction "A5_A5") (pintype "passive"))
      (node (ref "X14") (pin "A5") (pinfunction "A5_A5") (pintype "passive"))
      (node (ref "X15") (pin "A5") (pinfunction "A5_A5") (pintype "passive"))
      (node (ref "X16") (pin "A5") (pinfunction "A5_A5") (pintype "passive"))
      (node (ref "X17") (pin "A5") (pinfunction "A5_A5") (pintype "passive"))
      (node (ref "X18") (pin "A5") (pinfunction "A5_A5") (pintype "passive"))
      (node (ref "X2") (pin "A5") (pinfunction "A5_A5") (pintype "passive"))
      (node (ref "X3") (pin "A5") (pinfunction "A5_A5") (pintype "passive"))
      (node (ref "X4") (pin "A5") (pinfunction "A5_A5") (pintype "passive"))
      (node (ref "X5") (pin "A5") (pinfunction "A5_A5") (pintype "passive"))
      (node (ref "X6") (pin "A5") (pinfunction "A5_A5") (pintype "passive"))
      (node (ref "X7") (pin "A5") (pinfunction "A5_A5") (pintype "passive"))
      (node (ref "X8") (pin "A5") (pinfunction "A5_A5") (pintype "passive"))
      (node (ref "X9") (pin "A5") (pinfunction "A5_A5") (pintype "passive"))
    )
    (net (code "43") (name "/SS") (class "Default")
      (node (ref "X1") (pin "A4") (pinfunction "A4_A4") (pintype "passive"))
      (node (ref "X10") (pin "A4") (pinfunction "A4_A4") (pintype "passive"))
      (node (ref "X11") (pin "A4") (pinfunction "A4_A4") (pintype "passive"))
      (node (ref "X12") (pin "A4") (pinfunction "A4_A4") (pintype "passive"))
      (node (ref "X13") (pin "A4") (pinfunction "A4_A4") (pintype "passive"))
      (node (ref "X14") (pin "A4") (pinfunction "A4_A4") (pintype "passive"))
      (node (ref "X15") (pin "A4") (pinfunction "A4_A4") (pintype "passive"))
      (node (ref "X16") (pin "A4") (pinfunction "A4_A4") (pintype "passive"))
      (node (ref "X17") (pin "A4") (pinfunction "A4_A4") (pintype "passive"))
      (node (ref "X18") (pin "A4") (pinfunction "A4_A4") (pintype "passive"))
      (node (ref "X2") (pin "A4") (pinfunction "A4_A4") (pintype "passive"))
      (node (ref "X3") (pin "A4") (pinfunction "A4_A4") (pintype "passive"))
      (node (ref "X4") (pin "A4") (pinfunction "A4_A4") (pintype "passive"))
      (node (ref "X5") (pin "A4") (pinfunction "A4_A4") (pintype "passive"))
      (node (ref "X6") (pin "A4") (pinfunction "A4_A4") (pintype "passive"))
      (node (ref "X7") (pin "A4") (pinfunction "A4_A4") (pintype "passive"))
      (node (ref "X8") (pin "A4") (pinfunction "A4_A4") (pintype "passive"))
      (node (ref "X9") (pin "A4") (pinfunction "A4_A4") (pintype "passive"))
    )
    (net (code "44") (name "/UBL") (class "Default")
      (node (ref "X1") (pin "A8") (pinfunction "A8_A8") (pintype "passive"))
      (node (ref "X10") (pin "A8") (pinfunction "A8_A8") (pintype "passive"))
      (node (ref "X11") (pin "A8") (pinfunction "A8_A8") (pintype "passive"))
      (node (ref "X12") (pin "A8") (pinfunction "A8_A8") (pintype "passive"))
      (node (ref "X13") (pin "A8") (pinfunction "A8_A8") (pintype "passive"))
      (node (ref "X14") (pin "A8") (pinfunction "A8_A8") (pintype "passive"))
      (node (ref "X15") (pin "A8") (pinfunction "A8_A8") (pintype "passive"))
      (node (ref "X16") (pin "A8") (pinfunction "A8_A8") (pintype "passive"))
      (node (ref "X17") (pin "A8") (pinfunction "A8_A8") (pintype "passive"))
      (node (ref "X18") (pin "A8") (pinfunction "A8_A8") (pintype "passive"))
      (node (ref "X2") (pin "A8") (pinfunction "A8_A8") (pintype "passive"))
      (node (ref "X3") (pin "A8") (pinfunction "A8_A8") (pintype "passive"))
      (node (ref "X4") (pin "A8") (pinfunction "A8_A8") (pintype "passive"))
      (node (ref "X5") (pin "A8") (pinfunction "A8_A8") (pintype "passive"))
      (node (ref "X6") (pin "A8") (pinfunction "A8_A8") (pintype "passive"))
      (node (ref "X7") (pin "A8") (pinfunction "A8_A8") (pintype "passive"))
      (node (ref "X8") (pin "A8") (pinfunction "A8_A8") (pintype "passive"))
      (node (ref "X9") (pin "A8") (pinfunction "A8_A8") (pintype "passive"))
    )
    (net (code "45") (name "/WE") (class "Default")
      (node (ref "X1") (pin "C30") (pinfunction "C30_C30") (pintype "passive"))
      (node (ref "X10") (pin "C30") (pinfunction "C30_C30") (pintype "passive"))
      (node (ref "X11") (pin "C30") (pinfunction "C30_C30") (pintype "passive"))
      (node (ref "X12") (pin "C30") (pinfunction "C30_C30") (pintype "passive"))
      (node (ref "X13") (pin "C30") (pinfunction "C30_C30") (pintype "passive"))
      (node (ref "X14") (pin "C30") (pinfunction "C30_C30") (pintype "passive"))
      (node (ref "X15") (pin "C30") (pinfunction "C30_C30") (pintype "passive"))
      (node (ref "X16") (pin "C30") (pinfunction "C30_C30") (pintype "passive"))
      (node (ref "X17") (pin "C30") (pinfunction "C30_C30") (pintype "passive"))
      (node (ref "X18") (pin "C30") (pinfunction "C30_C30") (pintype "passive"))
      (node (ref "X2") (pin "C30") (pinfunction "C30_C30") (pintype "passive"))
      (node (ref "X3") (pin "C30") (pinfunction "C30_C30") (pintype "passive"))
      (node (ref "X4") (pin "C30") (pinfunction "C30_C30") (pintype "passive"))
      (node (ref "X5") (pin "C30") (pinfunction "C30_C30") (pintype "passive"))
      (node (ref "X6") (pin "C30") (pinfunction "C30_C30") (pintype "passive"))
      (node (ref "X7") (pin "C30") (pinfunction "C30_C30") (pintype "passive"))
      (node (ref "X8") (pin "C30") (pinfunction "C30_C30") (pintype "passive"))
      (node (ref "X9") (pin "C30") (pinfunction "C30_C30") (pintype "passive"))
    )
    (net (code "46") (name "GND") (class "Default")
      (node (ref "C1") (pin "1") (pinfunction "1_1") (pintype "passive"))
      (node (ref "C10") (pin "1") (pinfunction "1_1") (pintype "passive"))
      (node (ref "C11") (pin "1") (pinfunction "1_1") (pintype "passive"))
      (node (ref "C12") (pin "1") (pinfunction "1_1") (pintype "passive"))
      (node (ref "C13") (pin "1") (pinfunction "1_1") (pintype "passive"))
      (node (ref "C14") (pin "1") (pinfunction "1_1") (pintype "passive"))
      (node (ref "C15") (pin "1") (pinfunction "1_1") (pintype "passive"))
      (node (ref "C16") (pin "1") (pinfunction "1_1") (pintype "passive"))
      (node (ref "C17") (pin "1") (pinfunction "1_1") (pintype "passive"))
      (node (ref "C18") (pin "1") (pinfunction "1_1") (pintype "passive"))
      (node (ref "C2") (pin "1") (pinfunction "1_1") (pintype "passive"))
      (node (ref "C3") (pin "1") (pinfunction "1_1") (pintype "passive"))
      (node (ref "C4") (pin "1") (pinfunction "1_1") (pintype "passive"))
      (node (ref "C5") (pin "1") (pinfunction "1_1") (pintype "passive"))
      (node (ref "C6") (pin "1") (pinfunction "1_1") (pintype "passive"))
      (node (ref "C7") (pin "1") (pinfunction "1_1") (pintype "passive"))
      (node (ref "C8") (pin "1") (pinfunction "1_1") (pintype "passive"))
      (node (ref "C9") (pin "1") (pinfunction "1_1") (pintype "passive"))
      (node (ref "X1") (pin "A10") (pinfunction "A10_A10") (pintype "passive"))
      (node (ref "X1") (pin "A11") (pinfunction "A11_A11") (pintype "passive"))
      (node (ref "X1") (pin "A12") (pinfunction "A12_A12") (pintype "passive"))
      (node (ref "X1") (pin "A13") (pinfunction "A13_A13") (pintype "passive"))
      (node (ref "X1") (pin "A14") (pinfunction "A14_A14") (pintype "passive"))
      (node (ref "X1") (pin "A15") (pinfunction "A15_A15") (pintype "passive"))
      (node (ref "X1") (pin "A16") (pinfunction "A16_A16") (pintype "passive"))
      (node (ref "X1") (pin "A17") (pinfunction "A17_A17") (pintype "passive"))
      (node (ref "X1") (pin "A18") (pinfunction "A18_A18") (pintype "passive"))
      (node (ref "X1") (pin "A19") (pinfunction "A19_A19") (pintype "passive"))
      (node (ref "X1") (pin "A20") (pinfunction "A20_A20") (pintype "passive"))
      (node (ref "X1") (pin "A21") (pinfunction "A21_A21") (pintype "passive"))
      (node (ref "X1") (pin "A22") (pinfunction "A22_A22") (pintype "passive"))
      (node (ref "X1") (pin "A23") (pinfunction "A23_A23") (pintype "passive"))
      (node (ref "X1") (pin "A24") (pinfunction "A24_A24") (pintype "passive"))
      (node (ref "X1") (pin "A9") (pinfunction "A9_A9") (pintype "passive"))
      (node (ref "X10") (pin "A10") (pinfunction "A10_A10") (pintype "passive"))
      (node (ref "X10") (pin "A11") (pinfunction "A11_A11") (pintype "passive"))
      (node (ref "X10") (pin "A12") (pinfunction "A12_A12") (pintype "passive"))
      (node (ref "X10") (pin "A13") (pinfunction "A13_A13") (pintype "passive"))
      (node (ref "X10") (pin "A14") (pinfunction "A14_A14") (pintype "passive"))
      (node (ref "X10") (pin "A15") (pinfunction "A15_A15") (pintype "passive"))
      (node (ref "X10") (pin "A16") (pinfunction "A16_A16") (pintype "passive"))
      (node (ref "X10") (pin "A17") (pinfunction "A17_A17") (pintype "passive"))
      (node (ref "X10") (pin "A18") (pinfunction "A18_A18") (pintype "passive"))
      (node (ref "X10") (pin "A19") (pinfunction "A19_A19") (pintype "passive"))
      (node (ref "X10") (pin "A20") (pinfunction "A20_A20") (pintype "passive"))
      (node (ref "X10") (pin "A21") (pinfunction "A21_A21") (pintype "passive"))
      (node (ref "X10") (pin "A22") (pinfunction "A22_A22") (pintype "passive"))
      (node (ref "X10") (pin "A23") (pinfunction "A23_A23") (pintype "passive"))
      (node (ref "X10") (pin "A24") (pinfunction "A24_A24") (pintype "passive"))
      (node (ref "X10") (pin "A9") (pinfunction "A9_A9") (pintype "passive"))
      (node (ref "X11") (pin "A10") (pinfunction "A10_A10") (pintype "passive"))
      (node (ref "X11") (pin "A11") (pinfunction "A11_A11") (pintype "passive"))
      (node (ref "X11") (pin "A12") (pinfunction "A12_A12") (pintype "passive"))
      (node (ref "X11") (pin "A13") (pinfunction "A13_A13") (pintype "passive"))
      (node (ref "X11") (pin "A14") (pinfunction "A14_A14") (pintype "passive"))
      (node (ref "X11") (pin "A15") (pinfunction "A15_A15") (pintype "passive"))
      (node (ref "X11") (pin "A16") (pinfunction "A16_A16") (pintype "passive"))
      (node (ref "X11") (pin "A17") (pinfunction "A17_A17") (pintype "passive"))
      (node (ref "X11") (pin "A18") (pinfunction "A18_A18") (pintype "passive"))
      (node (ref "X11") (pin "A19") (pinfunction "A19_A19") (pintype "passive"))
      (node (ref "X11") (pin "A20") (pinfunction "A20_A20") (pintype "passive"))
      (node (ref "X11") (pin "A21") (pinfunction "A21_A21") (pintype "passive"))
      (node (ref "X11") (pin "A22") (pinfunction "A22_A22") (pintype "passive"))
      (node (ref "X11") (pin "A23") (pinfunction "A23_A23") (pintype "passive"))
      (node (ref "X11") (pin "A24") (pinfunction "A24_A24") (pintype "passive"))
      (node (ref "X11") (pin "A9") (pinfunction "A9_A9") (pintype "passive"))
      (node (ref "X12") (pin "A10") (pinfunction "A10_A10") (pintype "passive"))
      (node (ref "X12") (pin "A11") (pinfunction "A11_A11") (pintype "passive"))
      (node (ref "X12") (pin "A12") (pinfunction "A12_A12") (pintype "passive"))
      (node (ref "X12") (pin "A13") (pinfunction "A13_A13") (pintype "passive"))
      (node (ref "X12") (pin "A14") (pinfunction "A14_A14") (pintype "passive"))
      (node (ref "X12") (pin "A15") (pinfunction "A15_A15") (pintype "passive"))
      (node (ref "X12") (pin "A16") (pinfunction "A16_A16") (pintype "passive"))
      (node (ref "X12") (pin "A17") (pinfunction "A17_A17") (pintype "passive"))
      (node (ref "X12") (pin "A18") (pinfunction "A18_A18") (pintype "passive"))
      (node (ref "X12") (pin "A19") (pinfunction "A19_A19") (pintype "passive"))
      (node (ref "X12") (pin "A20") (pinfunction "A20_A20") (pintype "passive"))
      (node (ref "X12") (pin "A21") (pinfunction "A21_A21") (pintype "passive"))
      (node (ref "X12") (pin "A22") (pinfunction "A22_A22") (pintype "passive"))
      (node (ref "X12") (pin "A23") (pinfunction "A23_A23") (pintype "passive"))
      (node (ref "X12") (pin "A24") (pinfunction "A24_A24") (pintype "passive"))
      (node (ref "X12") (pin "A9") (pinfunction "A9_A9") (pintype "passive"))
      (node (ref "X13") (pin "A10") (pinfunction "A10_A10") (pintype "passive"))
      (node (ref "X13") (pin "A11") (pinfunction "A11_A11") (pintype "passive"))
      (node (ref "X13") (pin "A12") (pinfunction "A12_A12") (pintype "passive"))
      (node (ref "X13") (pin "A13") (pinfunction "A13_A13") (pintype "passive"))
      (node (ref "X13") (pin "A14") (pinfunction "A14_A14") (pintype "passive"))
      (node (ref "X13") (pin "A15") (pinfunction "A15_A15") (pintype "passive"))
      (node (ref "X13") (pin "A16") (pinfunction "A16_A16") (pintype "passive"))
      (node (ref "X13") (pin "A17") (pinfunction "A17_A17") (pintype "passive"))
      (node (ref "X13") (pin "A18") (pinfunction "A18_A18") (pintype "passive"))
      (node (ref "X13") (pin "A19") (pinfunction "A19_A19") (pintype "passive"))
      (node (ref "X13") (pin "A20") (pinfunction "A20_A20") (pintype "passive"))
      (node (ref "X13") (pin "A21") (pinfunction "A21_A21") (pintype "passive"))
      (node (ref "X13") (pin "A22") (pinfunction "A22_A22") (pintype "passive"))
      (node (ref "X13") (pin "A23") (pinfunction "A23_A23") (pintype "passive"))
      (node (ref "X13") (pin "A24") (pinfunction "A24_A24") (pintype "passive"))
      (node (ref "X13") (pin "A9") (pinfunction "A9_A9") (pintype "passive"))
      (node (ref "X14") (pin "A10") (pinfunction "A10_A10") (pintype "passive"))
      (node (ref "X14") (pin "A11") (pinfunction "A11_A11") (pintype "passive"))
      (node (ref "X14") (pin "A12") (pinfunction "A12_A12") (pintype "passive"))
      (node (ref "X14") (pin "A13") (pinfunction "A13_A13") (pintype "passive"))
      (node (ref "X14") (pin "A14") (pinfunction "A14_A14") (pintype "passive"))
      (node (ref "X14") (pin "A15") (pinfunction "A15_A15") (pintype "passive"))
      (node (ref "X14") (pin "A16") (pinfunction "A16_A16") (pintype "passive"))
      (node (ref "X14") (pin "A17") (pinfunction "A17_A17") (pintype "passive"))
      (node (ref "X14") (pin "A18") (pinfunction "A18_A18") (pintype "passive"))
      (node (ref "X14") (pin "A19") (pinfunction "A19_A19") (pintype "passive"))
      (node (ref "X14") (pin "A20") (pinfunction "A20_A20") (pintype "passive"))
      (node (ref "X14") (pin "A21") (pinfunction "A21_A21") (pintype "passive"))
      (node (ref "X14") (pin "A22") (pinfunction "A22_A22") (pintype "passive"))
      (node (ref "X14") (pin "A23") (pinfunction "A23_A23") (pintype "passive"))
      (node (ref "X14") (pin "A24") (pinfunction "A24_A24") (pintype "passive"))
      (node (ref "X14") (pin "A9") (pinfunction "A9_A9") (pintype "passive"))
      (node (ref "X15") (pin "A10") (pinfunction "A10_A10") (pintype "passive"))
      (node (ref "X15") (pin "A11") (pinfunction "A11_A11") (pintype "passive"))
      (node (ref "X15") (pin "A12") (pinfunction "A12_A12") (pintype "passive"))
      (node (ref "X15") (pin "A13") (pinfunction "A13_A13") (pintype "passive"))
      (node (ref "X15") (pin "A14") (pinfunction "A14_A14") (pintype "passive"))
      (node (ref "X15") (pin "A15") (pinfunction "A15_A15") (pintype "passive"))
      (node (ref "X15") (pin "A16") (pinfunction "A16_A16") (pintype "passive"))
      (node (ref "X15") (pin "A17") (pinfunction "A17_A17") (pintype "passive"))
      (node (ref "X15") (pin "A18") (pinfunction "A18_A18") (pintype "passive"))
      (node (ref "X15") (pin "A19") (pinfunction "A19_A19") (pintype "passive"))
      (node (ref "X15") (pin "A20") (pinfunction "A20_A20") (pintype "passive"))
      (node (ref "X15") (pin "A21") (pinfunction "A21_A21") (pintype "passive"))
      (node (ref "X15") (pin "A22") (pinfunction "A22_A22") (pintype "passive"))
      (node (ref "X15") (pin "A23") (pinfunction "A23_A23") (pintype "passive"))
      (node (ref "X15") (pin "A24") (pinfunction "A24_A24") (pintype "passive"))
      (node (ref "X15") (pin "A9") (pinfunction "A9_A9") (pintype "passive"))
      (node (ref "X16") (pin "A10") (pinfunction "A10_A10") (pintype "passive"))
      (node (ref "X16") (pin "A11") (pinfunction "A11_A11") (pintype "passive"))
      (node (ref "X16") (pin "A12") (pinfunction "A12_A12") (pintype "passive"))
      (node (ref "X16") (pin "A13") (pinfunction "A13_A13") (pintype "passive"))
      (node (ref "X16") (pin "A14") (pinfunction "A14_A14") (pintype "passive"))
      (node (ref "X16") (pin "A15") (pinfunction "A15_A15") (pintype "passive"))
      (node (ref "X16") (pin "A16") (pinfunction "A16_A16") (pintype "passive"))
      (node (ref "X16") (pin "A17") (pinfunction "A17_A17") (pintype "passive"))
      (node (ref "X16") (pin "A18") (pinfunction "A18_A18") (pintype "passive"))
      (node (ref "X16") (pin "A19") (pinfunction "A19_A19") (pintype "passive"))
      (node (ref "X16") (pin "A20") (pinfunction "A20_A20") (pintype "passive"))
      (node (ref "X16") (pin "A21") (pinfunction "A21_A21") (pintype "passive"))
      (node (ref "X16") (pin "A22") (pinfunction "A22_A22") (pintype "passive"))
      (node (ref "X16") (pin "A23") (pinfunction "A23_A23") (pintype "passive"))
      (node (ref "X16") (pin "A24") (pinfunction "A24_A24") (pintype "passive"))
      (node (ref "X16") (pin "A9") (pinfunction "A9_A9") (pintype "passive"))
      (node (ref "X17") (pin "A10") (pinfunction "A10_A10") (pintype "passive"))
      (node (ref "X17") (pin "A11") (pinfunction "A11_A11") (pintype "passive"))
      (node (ref "X17") (pin "A12") (pinfunction "A12_A12") (pintype "passive"))
      (node (ref "X17") (pin "A13") (pinfunction "A13_A13") (pintype "passive"))
      (node (ref "X17") (pin "A14") (pinfunction "A14_A14") (pintype "passive"))
      (node (ref "X17") (pin "A15") (pinfunction "A15_A15") (pintype "passive"))
      (node (ref "X17") (pin "A16") (pinfunction "A16_A16") (pintype "passive"))
      (node (ref "X17") (pin "A17") (pinfunction "A17_A17") (pintype "passive"))
      (node (ref "X17") (pin "A18") (pinfunction "A18_A18") (pintype "passive"))
      (node (ref "X17") (pin "A19") (pinfunction "A19_A19") (pintype "passive"))
      (node (ref "X17") (pin "A20") (pinfunction "A20_A20") (pintype "passive"))
      (node (ref "X17") (pin "A21") (pinfunction "A21_A21") (pintype "passive"))
      (node (ref "X17") (pin "A22") (pinfunction "A22_A22") (pintype "passive"))
      (node (ref "X17") (pin "A23") (pinfunction "A23_A23") (pintype "passive"))
      (node (ref "X17") (pin "A24") (pinfunction "A24_A24") (pintype "passive"))
      (node (ref "X17") (pin "A9") (pinfunction "A9_A9") (pintype "passive"))
      (node (ref "X18") (pin "A10") (pinfunction "A10_A10") (pintype "passive"))
      (node (ref "X18") (pin "A11") (pinfunction "A11_A11") (pintype "passive"))
      (node (ref "X18") (pin "A12") (pinfunction "A12_A12") (pintype "passive"))
      (node (ref "X18") (pin "A13") (pinfunction "A13_A13") (pintype "passive"))
      (node (ref "X18") (pin "A14") (pinfunction "A14_A14") (pintype "passive"))
      (node (ref "X18") (pin "A15") (pinfunction "A15_A15") (pintype "passive"))
      (node (ref "X18") (pin "A16") (pinfunction "A16_A16") (pintype "passive"))
      (node (ref "X18") (pin "A17") (pinfunction "A17_A17") (pintype "passive"))
      (node (ref "X18") (pin "A18") (pinfunction "A18_A18") (pintype "passive"))
      (node (ref "X18") (pin "A19") (pinfunction "A19_A19") (pintype "passive"))
      (node (ref "X18") (pin "A20") (pinfunction "A20_A20") (pintype "passive"))
      (node (ref "X18") (pin "A21") (pinfunction "A21_A21") (pintype "passive"))
      (node (ref "X18") (pin "A22") (pinfunction "A22_A22") (pintype "passive"))
      (node (ref "X18") (pin "A23") (pinfunction "A23_A23") (pintype "passive"))
      (node (ref "X18") (pin "A24") (pinfunction "A24_A24") (pintype "passive"))
      (node (ref "X18") (pin "A9") (pinfunction "A9_A9") (pintype "passive"))
      (node (ref "X19") (pin "2") (pinfunction "SK_2") (pintype "passive"))
      (node (ref "X2") (pin "A10") (pinfunction "A10_A10") (pintype "passive"))
      (node (ref "X2") (pin "A11") (pinfunction "A11_A11") (pintype "passive"))
      (node (ref "X2") (pin "A12") (pinfunction "A12_A12") (pintype "passive"))
      (node (ref "X2") (pin "A13") (pinfunction "A13_A13") (pintype "passive"))
      (node (ref "X2") (pin "A14") (pinfunction "A14_A14") (pintype "passive"))
      (node (ref "X2") (pin "A15") (pinfunction "A15_A15") (pintype "passive"))
      (node (ref "X2") (pin "A16") (pinfunction "A16_A16") (pintype "passive"))
      (node (ref "X2") (pin "A17") (pinfunction "A17_A17") (pintype "passive"))
      (node (ref "X2") (pin "A18") (pinfunction "A18_A18") (pintype "passive"))
      (node (ref "X2") (pin "A19") (pinfunction "A19_A19") (pintype "passive"))
      (node (ref "X2") (pin "A20") (pinfunction "A20_A20") (pintype "passive"))
      (node (ref "X2") (pin "A21") (pinfunction "A21_A21") (pintype "passive"))
      (node (ref "X2") (pin "A22") (pinfunction "A22_A22") (pintype "passive"))
      (node (ref "X2") (pin "A23") (pinfunction "A23_A23") (pintype "passive"))
      (node (ref "X2") (pin "A24") (pinfunction "A24_A24") (pintype "passive"))
      (node (ref "X2") (pin "A9") (pinfunction "A9_A9") (pintype "passive"))
      (node (ref "X3") (pin "A10") (pinfunction "A10_A10") (pintype "passive"))
      (node (ref "X3") (pin "A11") (pinfunction "A11_A11") (pintype "passive"))
      (node (ref "X3") (pin "A12") (pinfunction "A12_A12") (pintype "passive"))
      (node (ref "X3") (pin "A13") (pinfunction "A13_A13") (pintype "passive"))
      (node (ref "X3") (pin "A14") (pinfunction "A14_A14") (pintype "passive"))
      (node (ref "X3") (pin "A15") (pinfunction "A15_A15") (pintype "passive"))
      (node (ref "X3") (pin "A16") (pinfunction "A16_A16") (pintype "passive"))
      (node (ref "X3") (pin "A17") (pinfunction "A17_A17") (pintype "passive"))
      (node (ref "X3") (pin "A18") (pinfunction "A18_A18") (pintype "passive"))
      (node (ref "X3") (pin "A19") (pinfunction "A19_A19") (pintype "passive"))
      (node (ref "X3") (pin "A20") (pinfunction "A20_A20") (pintype "passive"))
      (node (ref "X3") (pin "A21") (pinfunction "A21_A21") (pintype "passive"))
      (node (ref "X3") (pin "A22") (pinfunction "A22_A22") (pintype "passive"))
      (node (ref "X3") (pin "A23") (pinfunction "A23_A23") (pintype "passive"))
      (node (ref "X3") (pin "A24") (pinfunction "A24_A24") (pintype "passive"))
      (node (ref "X3") (pin "A9") (pinfunction "A9_A9") (pintype "passive"))
      (node (ref "X4") (pin "A10") (pinfunction "A10_A10") (pintype "passive"))
      (node (ref "X4") (pin "A11") (pinfunction "A11_A11") (pintype "passive"))
      (node (ref "X4") (pin "A12") (pinfunction "A12_A12") (pintype "passive"))
      (node (ref "X4") (pin "A13") (pinfunction "A13_A13") (pintype "passive"))
      (node (ref "X4") (pin "A14") (pinfunction "A14_A14") (pintype "passive"))
      (node (ref "X4") (pin "A15") (pinfunction "A15_A15") (pintype "passive"))
      (node (ref "X4") (pin "A16") (pinfunction "A16_A16") (pintype "passive"))
      (node (ref "X4") (pin "A17") (pinfunction "A17_A17") (pintype "passive"))
      (node (ref "X4") (pin "A18") (pinfunction "A18_A18") (pintype "passive"))
      (node (ref "X4") (pin "A19") (pinfunction "A19_A19") (pintype "passive"))
      (node (ref "X4") (pin "A20") (pinfunction "A20_A20") (pintype "passive"))
      (node (ref "X4") (pin "A21") (pinfunction "A21_A21") (pintype "passive"))
      (node (ref "X4") (pin "A22") (pinfunction "A22_A22") (pintype "passive"))
      (node (ref "X4") (pin "A23") (pinfunction "A23_A23") (pintype "passive"))
      (node (ref "X4") (pin "A24") (pinfunction "A24_A24") (pintype "passive"))
      (node (ref "X4") (pin "A9") (pinfunction "A9_A9") (pintype "passive"))
      (node (ref "X5") (pin "A10") (pinfunction "A10_A10") (pintype "passive"))
      (node (ref "X5") (pin "A11") (pinfunction "A11_A11") (pintype "passive"))
      (node (ref "X5") (pin "A12") (pinfunction "A12_A12") (pintype "passive"))
      (node (ref "X5") (pin "A13") (pinfunction "A13_A13") (pintype "passive"))
      (node (ref "X5") (pin "A14") (pinfunction "A14_A14") (pintype "passive"))
      (node (ref "X5") (pin "A15") (pinfunction "A15_A15") (pintype "passive"))
      (node (ref "X5") (pin "A16") (pinfunction "A16_A16") (pintype "passive"))
      (node (ref "X5") (pin "A17") (pinfunction "A17_A17") (pintype "passive"))
      (node (ref "X5") (pin "A18") (pinfunction "A18_A18") (pintype "passive"))
      (node (ref "X5") (pin "A19") (pinfunction "A19_A19") (pintype "passive"))
      (node (ref "X5") (pin "A20") (pinfunction "A20_A20") (pintype "passive"))
      (node (ref "X5") (pin "A21") (pinfunction "A21_A21") (pintype "passive"))
      (node (ref "X5") (pin "A22") (pinfunction "A22_A22") (pintype "passive"))
      (node (ref "X5") (pin "A23") (pinfunction "A23_A23") (pintype "passive"))
      (node (ref "X5") (pin "A24") (pinfunction "A24_A24") (pintype "passive"))
      (node (ref "X5") (pin "A9") (pinfunction "A9_A9") (pintype "passive"))
      (node (ref "X6") (pin "A10") (pinfunction "A10_A10") (pintype "passive"))
      (node (ref "X6") (pin "A11") (pinfunction "A11_A11") (pintype "passive"))
      (node (ref "X6") (pin "A12") (pinfunction "A12_A12") (pintype "passive"))
      (node (ref "X6") (pin "A13") (pinfunction "A13_A13") (pintype "passive"))
      (node (ref "X6") (pin "A14") (pinfunction "A14_A14") (pintype "passive"))
      (node (ref "X6") (pin "A15") (pinfunction "A15_A15") (pintype "passive"))
      (node (ref "X6") (pin "A16") (pinfunction "A16_A16") (pintype "passive"))
      (node (ref "X6") (pin "A17") (pinfunction "A17_A17") (pintype "passive"))
      (node (ref "X6") (pin "A18") (pinfunction "A18_A18") (pintype "passive"))
      (node (ref "X6") (pin "A19") (pinfunction "A19_A19") (pintype "passive"))
      (node (ref "X6") (pin "A20") (pinfunction "A20_A20") (pintype "passive"))
      (node (ref "X6") (pin "A21") (pinfunction "A21_A21") (pintype "passive"))
      (node (ref "X6") (pin "A22") (pinfunction "A22_A22") (pintype "passive"))
      (node (ref "X6") (pin "A23") (pinfunction "A23_A23") (pintype "passive"))
      (node (ref "X6") (pin "A24") (pinfunction "A24_A24") (pintype "passive"))
      (node (ref "X6") (pin "A9") (pinfunction "A9_A9") (pintype "passive"))
      (node (ref "X7") (pin "A10") (pinfunction "A10_A10") (pintype "passive"))
      (node (ref "X7") (pin "A11") (pinfunction "A11_A11") (pintype "passive"))
      (node (ref "X7") (pin "A12") (pinfunction "A12_A12") (pintype "passive"))
      (node (ref "X7") (pin "A13") (pinfunction "A13_A13") (pintype "passive"))
      (node (ref "X7") (pin "A14") (pinfunction "A14_A14") (pintype "passive"))
      (node (ref "X7") (pin "A15") (pinfunction "A15_A15") (pintype "passive"))
      (node (ref "X7") (pin "A16") (pinfunction "A16_A16") (pintype "passive"))
      (node (ref "X7") (pin "A17") (pinfunction "A17_A17") (pintype "passive"))
      (node (ref "X7") (pin "A18") (pinfunction "A18_A18") (pintype "passive"))
      (node (ref "X7") (pin "A19") (pinfunction "A19_A19") (pintype "passive"))
      (node (ref "X7") (pin "A20") (pinfunction "A20_A20") (pintype "passive"))
      (node (ref "X7") (pin "A21") (pinfunction "A21_A21") (pintype "passive"))
      (node (ref "X7") (pin "A22") (pinfunction "A22_A22") (pintype "passive"))
      (node (ref "X7") (pin "A23") (pinfunction "A23_A23") (pintype "passive"))
      (node (ref "X7") (pin "A24") (pinfunction "A24_A24") (pintype "passive"))
      (node (ref "X7") (pin "A9") (pinfunction "A9_A9") (pintype "passive"))
      (node (ref "X8") (pin "A10") (pinfunction "A10_A10") (pintype "passive"))
      (node (ref "X8") (pin "A11") (pinfunction "A11_A11") (pintype "passive"))
      (node (ref "X8") (pin "A12") (pinfunction "A12_A12") (pintype "passive"))
      (node (ref "X8") (pin "A13") (pinfunction "A13_A13") (pintype "passive"))
      (node (ref "X8") (pin "A14") (pinfunction "A14_A14") (pintype "passive"))
      (node (ref "X8") (pin "A15") (pinfunction "A15_A15") (pintype "passive"))
      (node (ref "X8") (pin "A16") (pinfunction "A16_A16") (pintype "passive"))
      (node (ref "X8") (pin "A17") (pinfunction "A17_A17") (pintype "passive"))
      (node (ref "X8") (pin "A18") (pinfunction "A18_A18") (pintype "passive"))
      (node (ref "X8") (pin "A19") (pinfunction "A19_A19") (pintype "passive"))
      (node (ref "X8") (pin "A20") (pinfunction "A20_A20") (pintype "passive"))
      (node (ref "X8") (pin "A21") (pinfunction "A21_A21") (pintype "passive"))
      (node (ref "X8") (pin "A22") (pinfunction "A22_A22") (pintype "passive"))
      (node (ref "X8") (pin "A23") (pinfunction "A23_A23") (pintype "passive"))
      (node (ref "X8") (pin "A24") (pinfunction "A24_A24") (pintype "passive"))
      (node (ref "X8") (pin "A9") (pinfunction "A9_A9") (pintype "passive"))
      (node (ref "X9") (pin "A10") (pinfunction "A10_A10") (pintype "passive"))
      (node (ref "X9") (pin "A11") (pinfunction "A11_A11") (pintype "passive"))
      (node (ref "X9") (pin "A12") (pinfunction "A12_A12") (pintype "passive"))
      (node (ref "X9") (pin "A13") (pinfunction "A13_A13") (pintype "passive"))
      (node (ref "X9") (pin "A14") (pinfunction "A14_A14") (pintype "passive"))
      (node (ref "X9") (pin "A15") (pinfunction "A15_A15") (pintype "passive"))
      (node (ref "X9") (pin "A16") (pinfunction "A16_A16") (pintype "passive"))
      (node (ref "X9") (pin "A17") (pinfunction "A17_A17") (pintype "passive"))
      (node (ref "X9") (pin "A18") (pinfunction "A18_A18") (pintype "passive"))
      (node (ref "X9") (pin "A19") (pinfunction "A19_A19") (pintype "passive"))
      (node (ref "X9") (pin "A20") (pinfunction "A20_A20") (pintype "passive"))
      (node (ref "X9") (pin "A21") (pinfunction "A21_A21") (pintype "passive"))
      (node (ref "X9") (pin "A22") (pinfunction "A22_A22") (pintype "passive"))
      (node (ref "X9") (pin "A23") (pinfunction "A23_A23") (pintype "passive"))
      (node (ref "X9") (pin "A24") (pinfunction "A24_A24") (pintype "passive"))
      (node (ref "X9") (pin "A9") (pinfunction "A9_A9") (pintype "passive"))
    )
  )
)
